# control_board.net
KiCad netlist of a schematic drawn in EasyEDA Pro
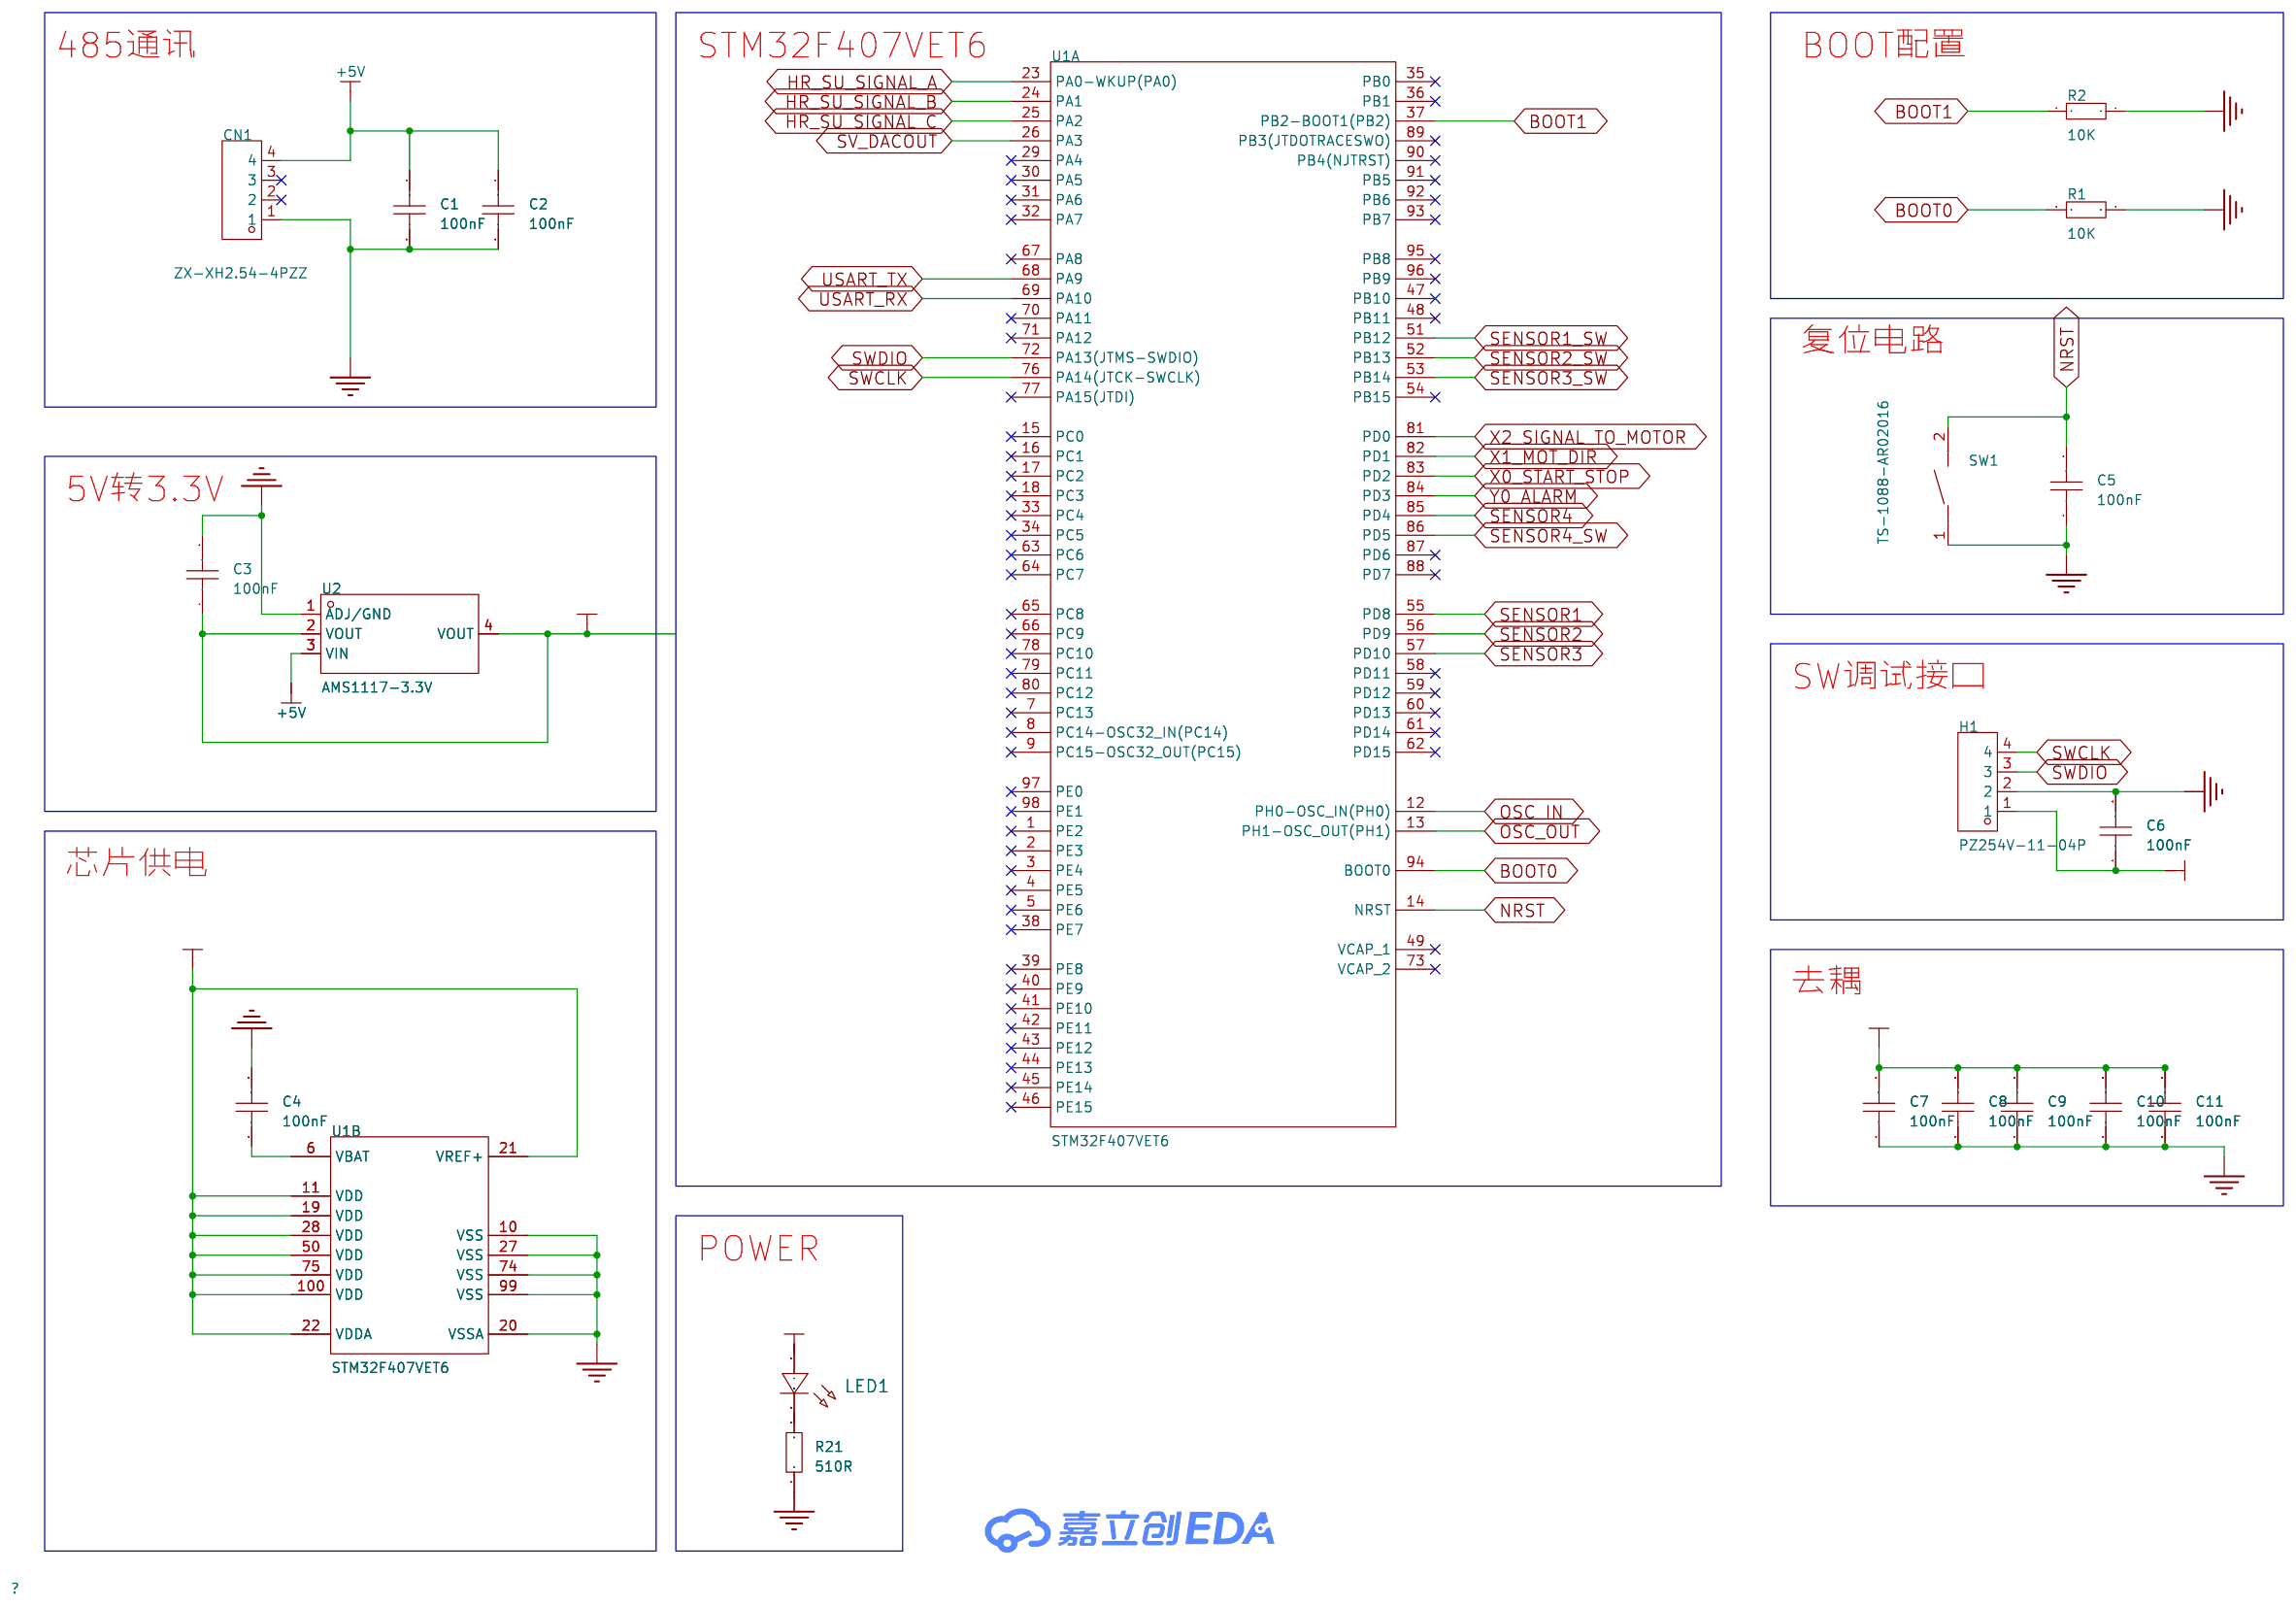
[diagram p0: P1]
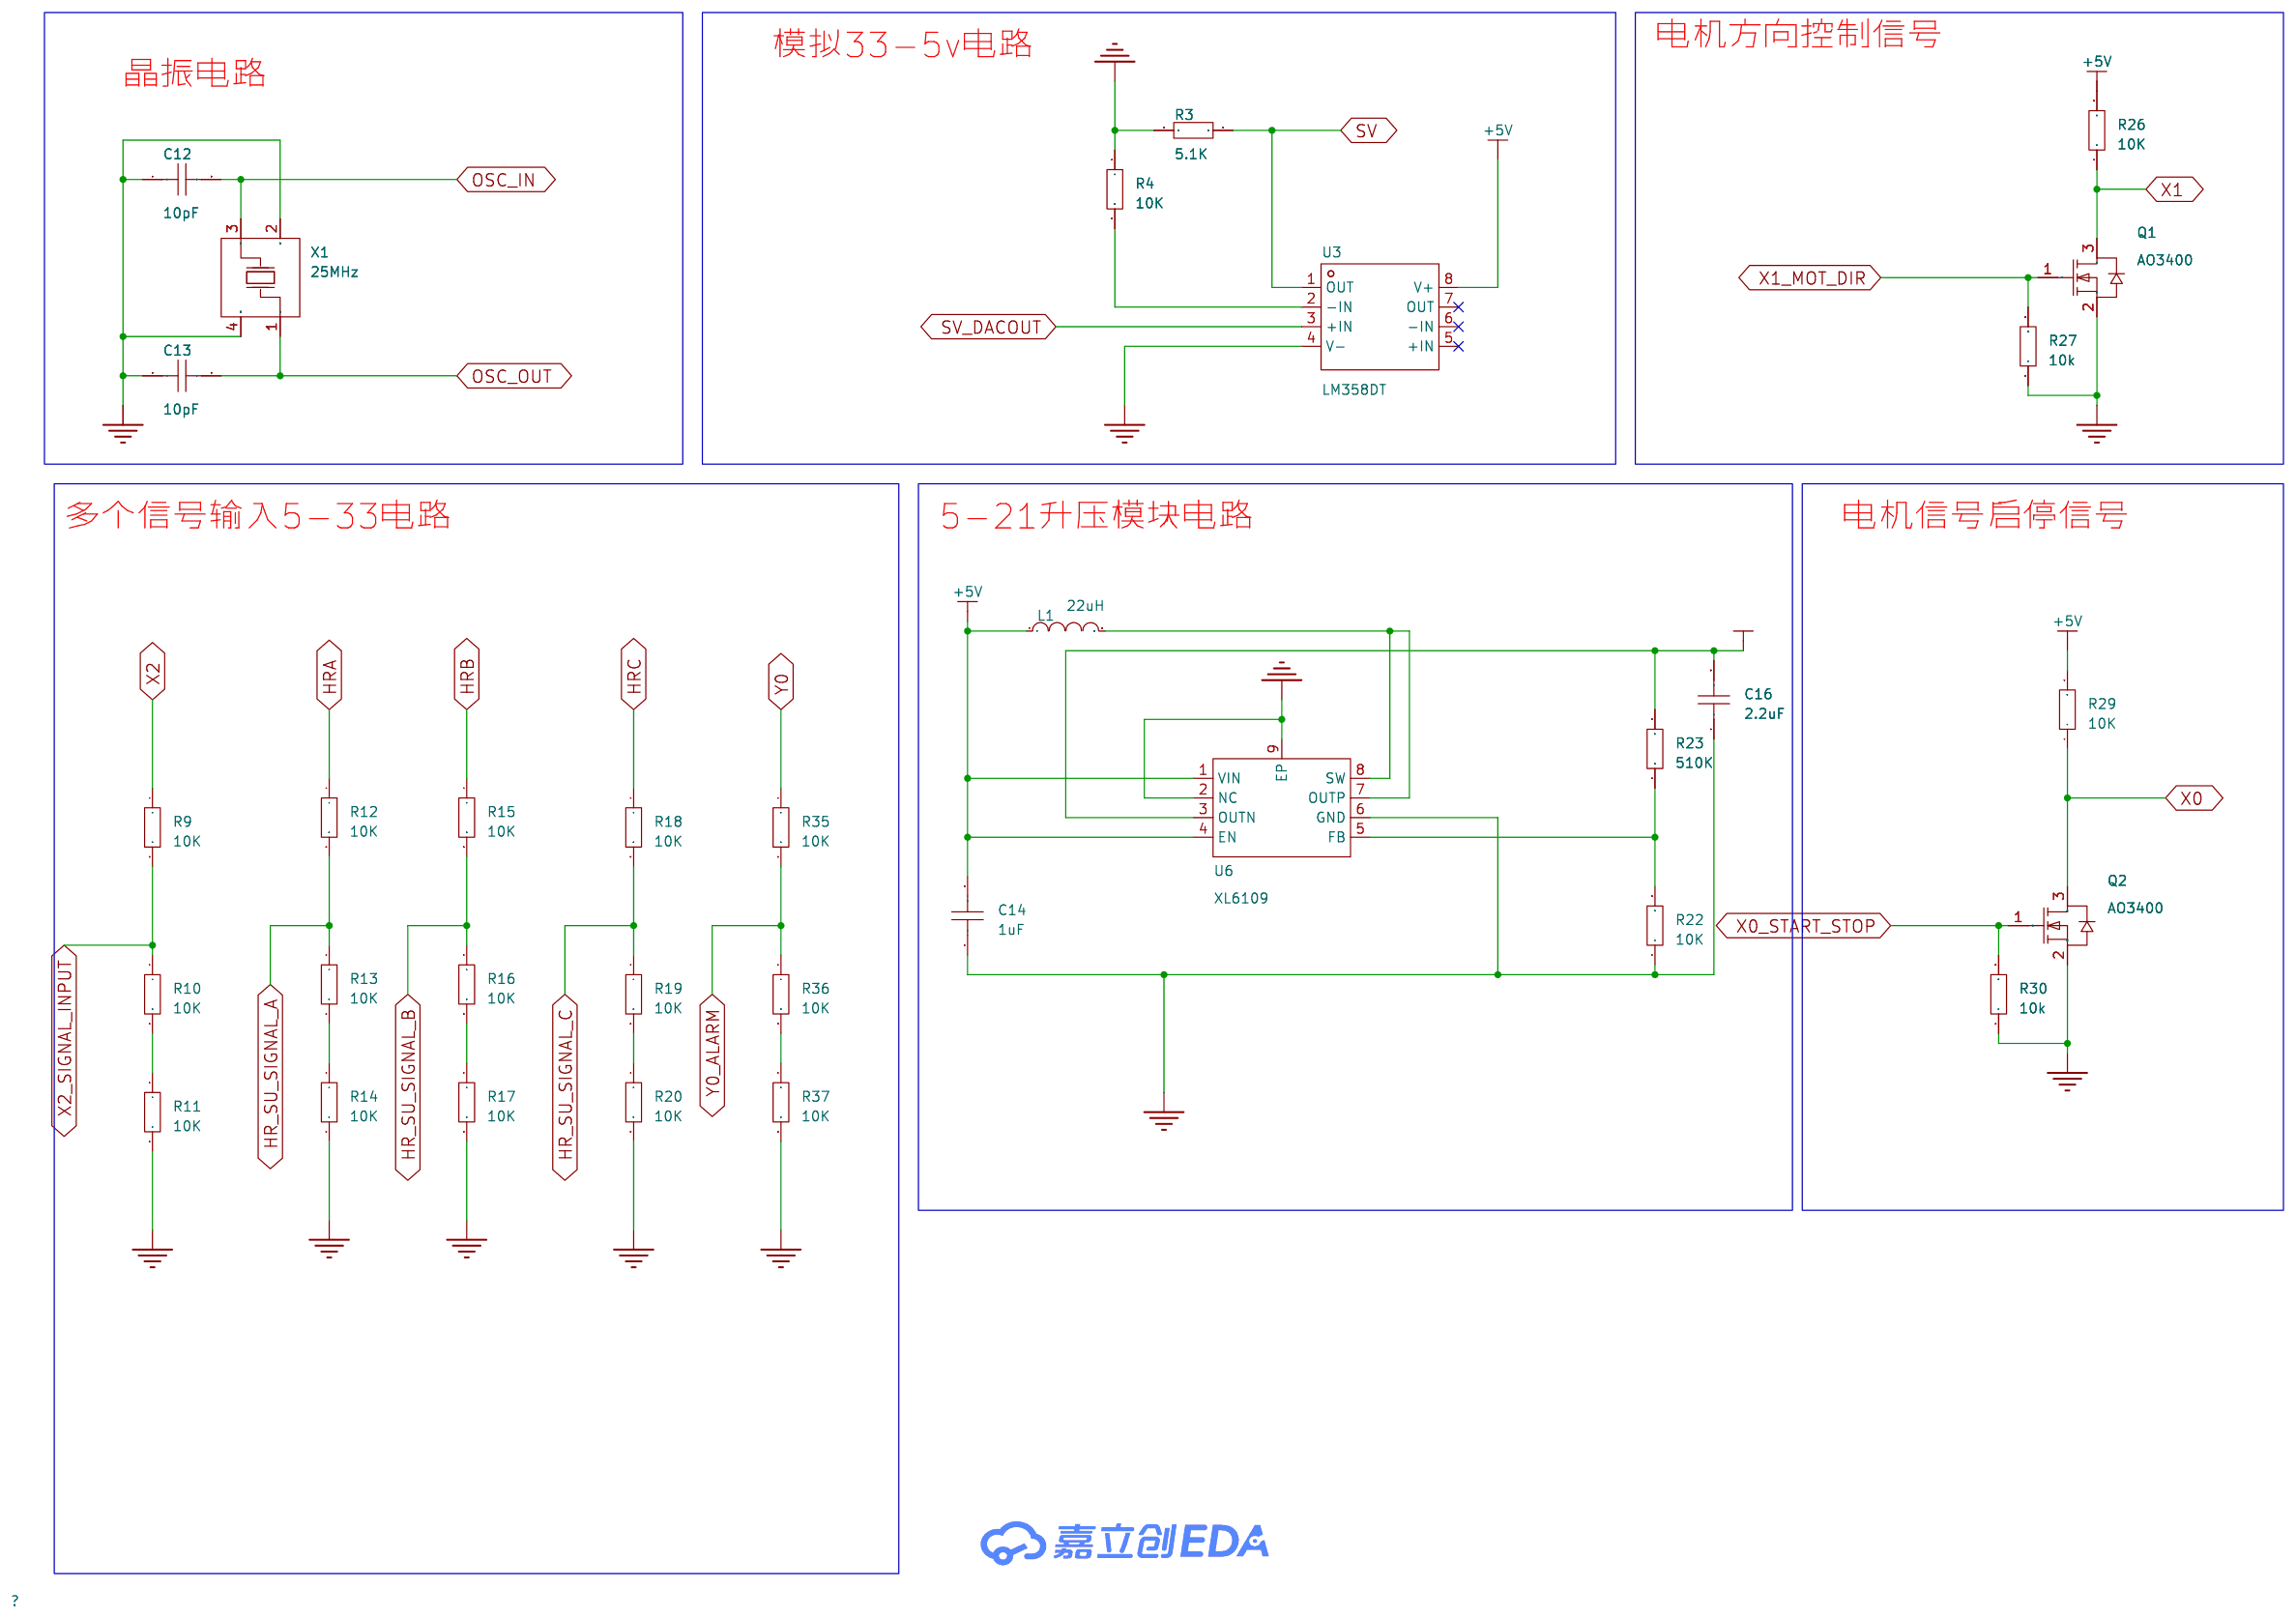
[diagram p1: P2]
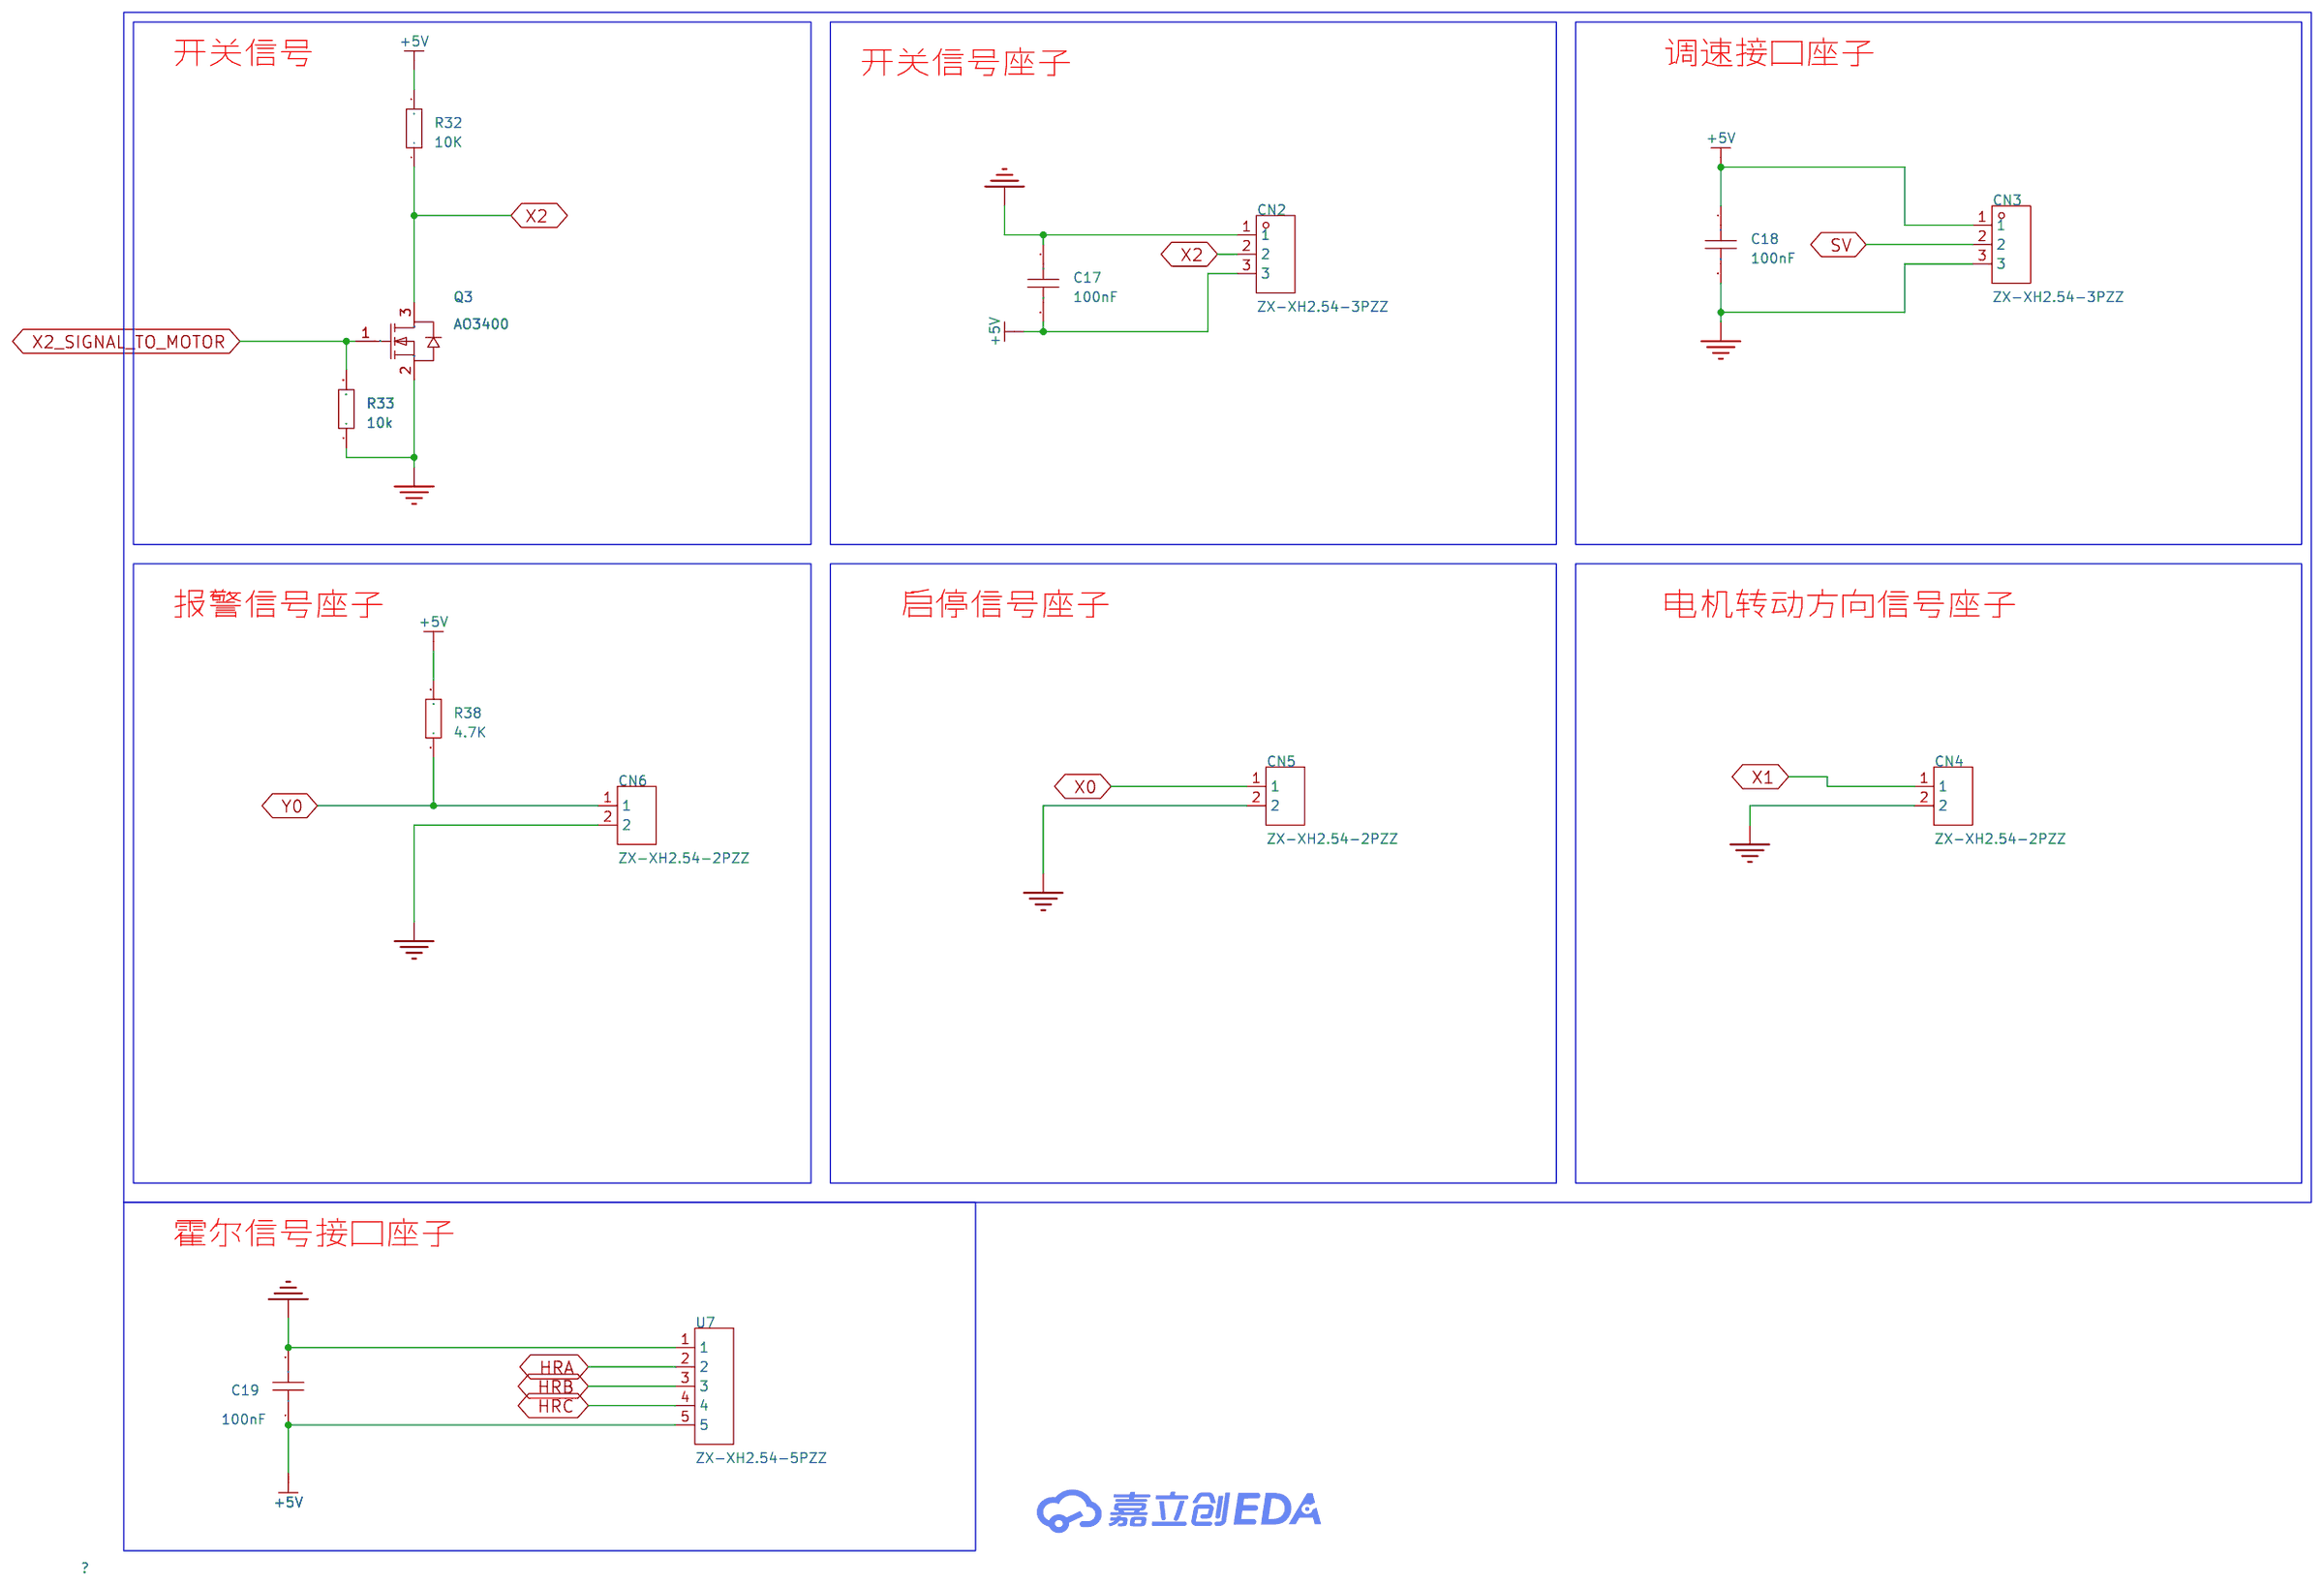
[diagram p2: P3]
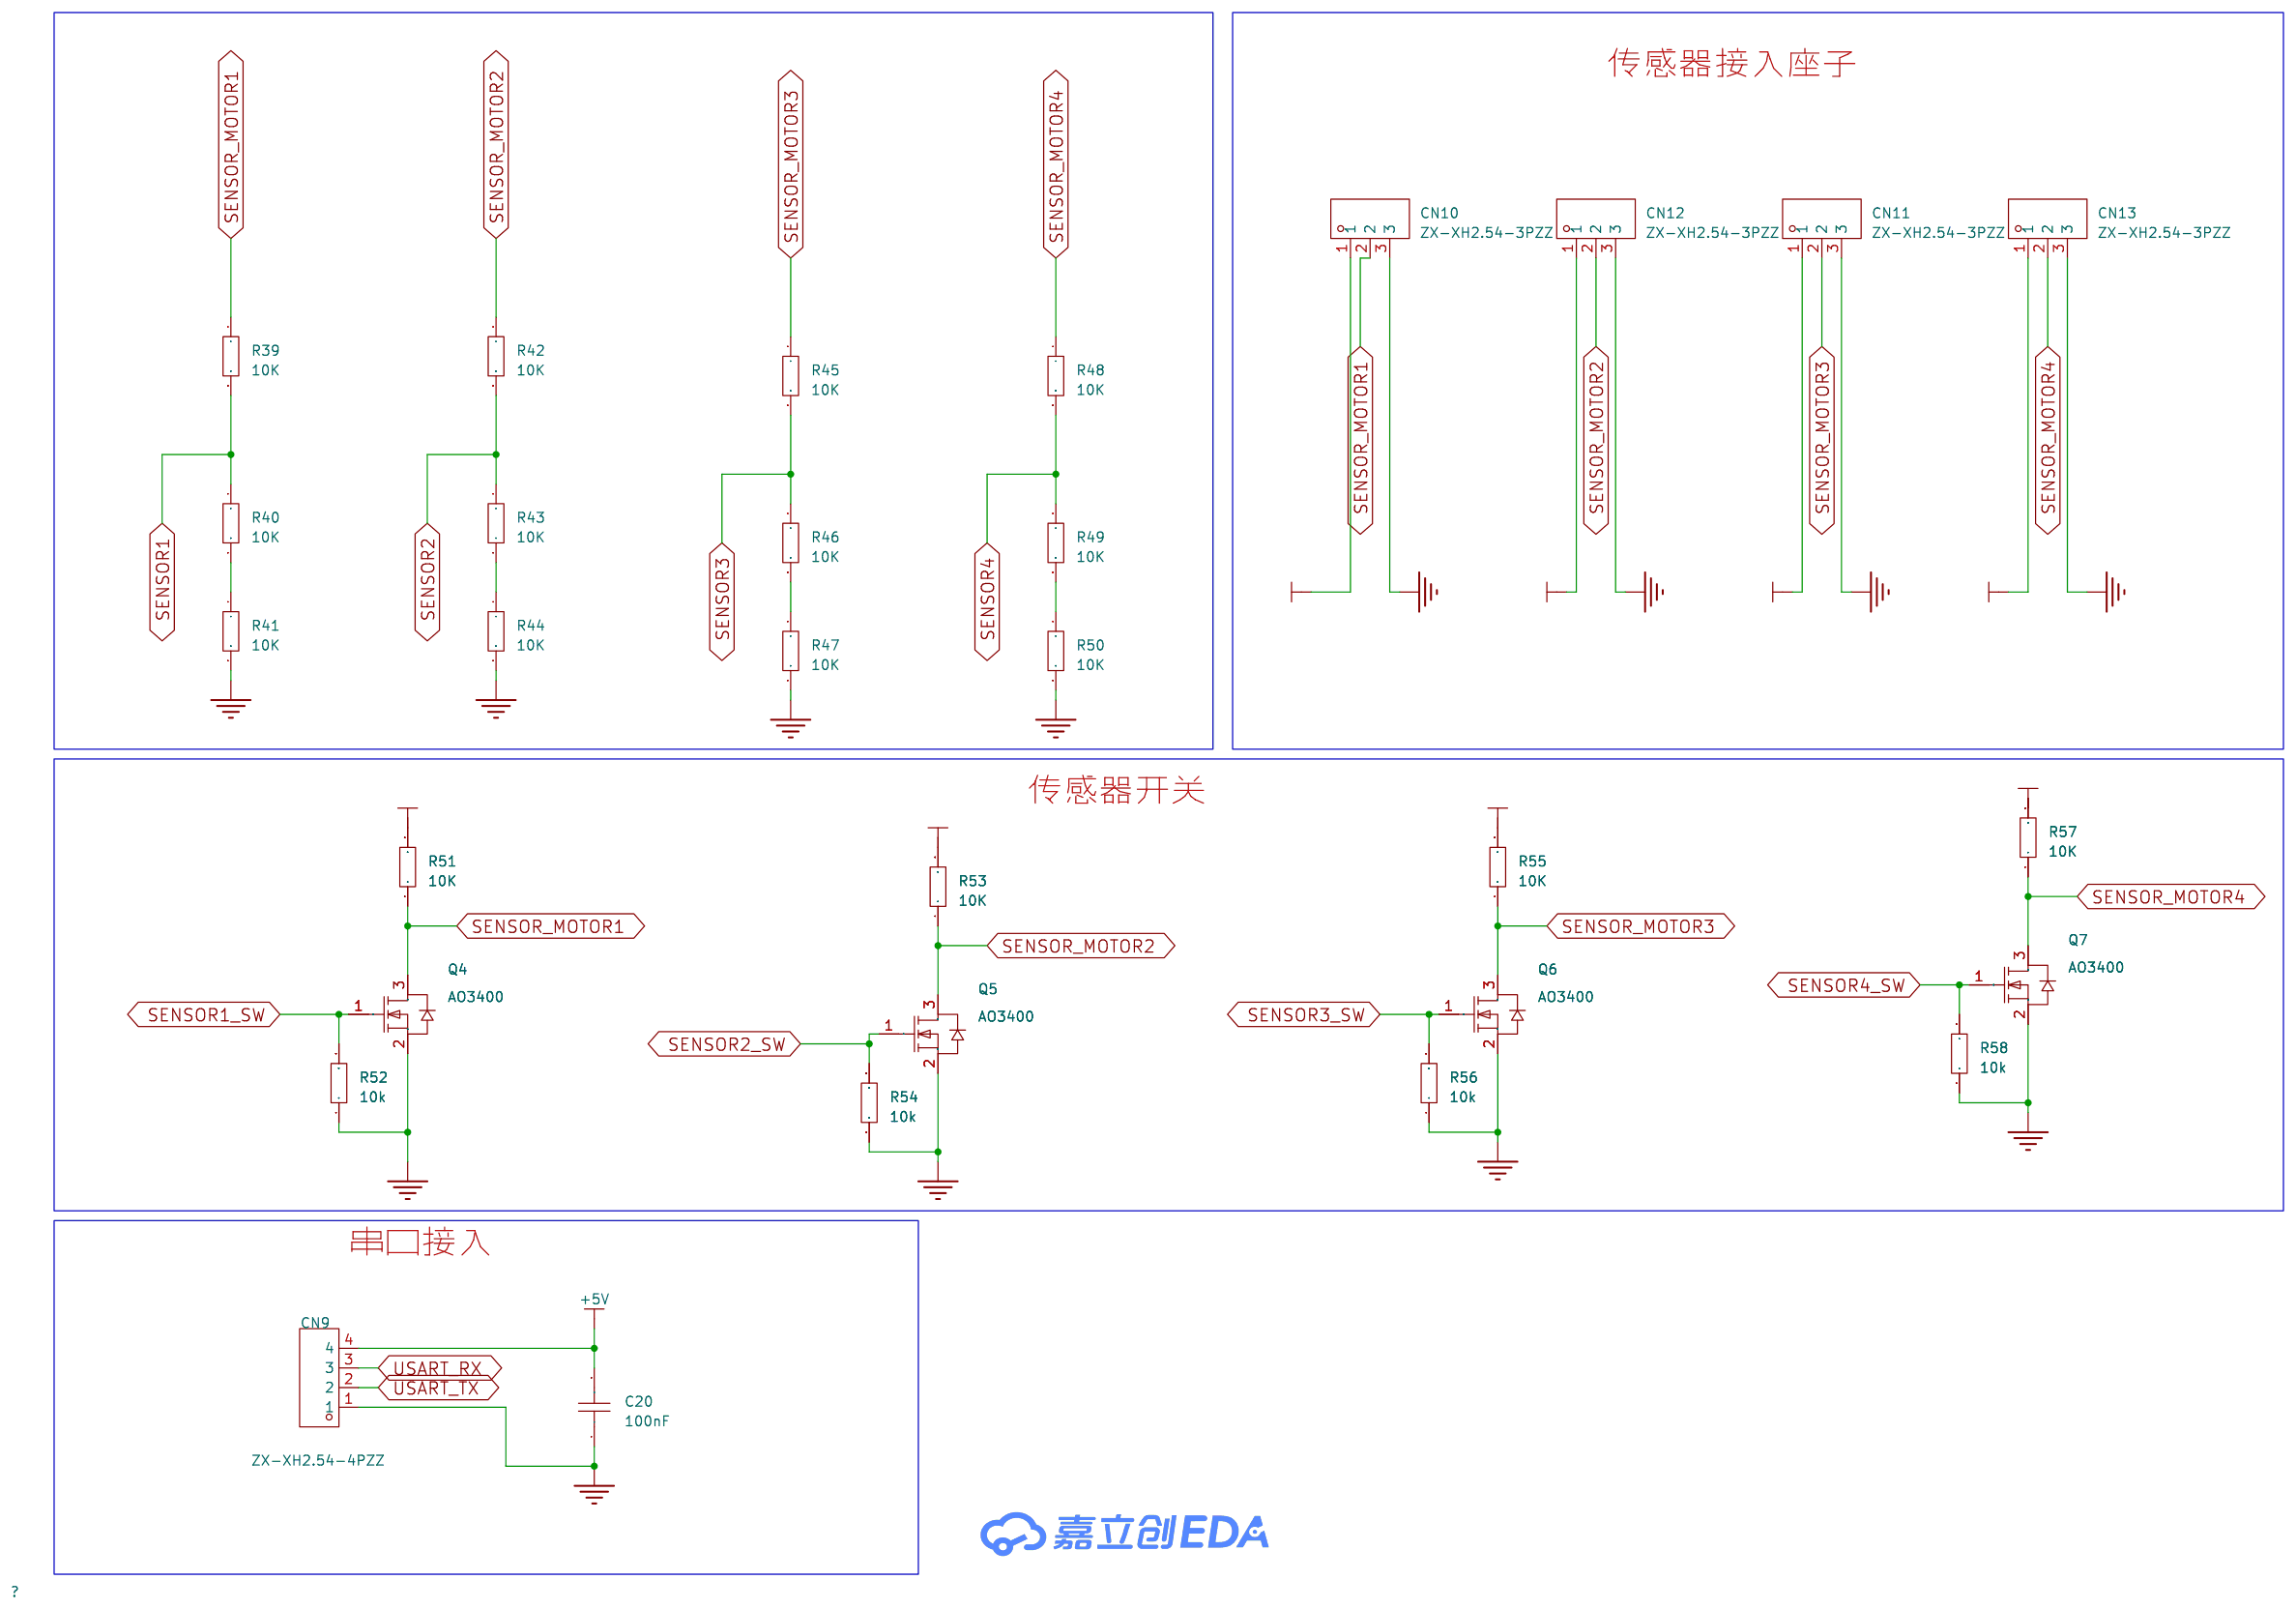
[diagram p3: P4]

(export (version "E")
  (design (tool "Eeschema 10.0.6"))
  (components
    (comp (ref "C1")
      (value "100nF")
      (footprint "easyedapro:C0603")
      (libsource (lib "easyedapro") (part "CapAcitance"))
    )
    (comp (ref "C2")
      (value "100nF")
      (footprint "easyedapro:C0603")
      (libsource (lib "easyedapro") (part "CapAcitance"))
    )
    (comp (ref "C3")
      (value "100nF")
      (footprint "easyedapro:C0603")
      (libsource (lib "easyedapro") (part "CapAcitance"))
    )
    (comp (ref "C4")
      (value "100nF")
      (footprint "easyedapro:C0603")
      (libsource (lib "easyedapro") (part "CapAcitance"))
    )
    (comp (ref "C5")
      (value "100nF")
      (footprint "easyedapro:C0603")
      (libsource (lib "easyedapro") (part "CapAcitance"))
    )
    (comp (ref "C6")
      (value "100nF")
      (footprint "easyedapro:C0603")
      (libsource (lib "easyedapro") (part "CapAcitance"))
    )
    (comp (ref "C7")
      (value "100nF")
      (footprint "easyedapro:C0603")
      (libsource (lib "easyedapro") (part "CapAcitance"))
    )
    (comp (ref "C8")
      (value "100nF")
      (footprint "easyedapro:C0603")
      (libsource (lib "easyedapro") (part "CapAcitance"))
    )
    (comp (ref "C9")
      (value "100nF")
      (footprint "easyedapro:C0603")
      (libsource (lib "easyedapro") (part "CapAcitance"))
    )
    (comp (ref "C10")
      (value "100nF")
      (footprint "easyedapro:C0603")
      (libsource (lib "easyedapro") (part "CapAcitance"))
    )
    (comp (ref "C11")
      (value "100nF")
      (footprint "easyedapro:C0603")
      (libsource (lib "easyedapro") (part "CapAcitance"))
    )
    (comp (ref "CN1")
      (value "ZX-XH2.54-4PZZ")
      (footprint "easyedapro:CONN-TH_4P-P2.50_4PIN")
      (fields (field (name "Manufacturer") "Megastar(兆星)"))
      (libsource (lib "easyedapro") (part "ZX-XH2.54-4PZZ"))
    )
    (comp (ref "H1")
      (value "PZ254V-11-04P")
      (footprint "easyedapro:HDR-TH_4P-P2.54-V-M")
      (fields (field (name "Manufacturer") "XFCN(兴飞)"))
      (libsource (lib "easyedapro") (part "PZ254V-11-04P_C2691448"))
    )
    (comp (ref "LED1")
      (value "~")
      (footprint "easyedapro:LED_0603")
      (libsource (lib "easyedapro") (part "LED_R"))
    )
    (comp (ref "R1") (value "10K") (footprint "easyedapro:R0603") (libsource (lib "easyedapro") (part "电阻")))
    (comp (ref "R2") (value "10K") (footprint "easyedapro:R0603") (libsource (lib "easyedapro") (part "电阻")))
    (comp (ref "R21")
      (value "510R")
      (footprint "easyedapro:R0603")
      (libsource (lib "easyedapro") (part "电阻"))
    )
    (comp (ref "SW1")
      (value "TS-1088-AR02016")
      (footprint "easyedapro:SW-SMD_L3.9-W3.0-P4.45")
      (fields (field (name "Manufacturer") "XUNPU(讯普)"))
      (libsource (lib "easyedapro") (part "TS-1088-AR02016"))
    )
    (comp (ref "U1")
      (value "STM32F407VET6")
      (footprint "easyedapro:LQFP-100_L14.0-W14.0-P0.50-LS16.0-BL")
      (description "CPU内核:ARM-M4;CPU最大主频:168MHz;应用领域:-;")
      (fields (field (name "Manufacturer") "ST(意法半导体)"))
      (libsource (lib "easyedapro") (part "STM32F407VET6"))
    )
    (comp (ref "U2")
      (value "AMS1117-3.3V")
      (footprint "easyedapro:SOT-223-4_L6.5-W3.5-P2.30-LS7.0-TR")
      (description "输出类型:固定;最大输入电压:18V;输出电压:3.3V;最大输出电流:1A;输出极性:正极;")
      (fields (field (name "Manufacturer") "MSKSEMI(美森科)"))
      (libsource (lib "easyedapro") (part "AMS1117-3.3V_C5120765"))
    )
    (comp (ref "C12")
      (value "10pF")
      (footprint "easyedapro:C0603")
      (libsource (lib "easyedapro") (part "CapAcitance"))
    )
    (comp (ref "C13")
      (value "10pF")
      (footprint "easyedapro:C0603")
      (libsource (lib "easyedapro") (part "CapAcitance"))
    )
    (comp (ref "C14")
      (value "1uF")
      (footprint "easyedapro:C0603")
      (libsource (lib "easyedapro") (part "CapAcitance"))
    )
    (comp (ref "C16")
      (value "2.2uF")
      (footprint "easyedapro:C0603")
      (libsource (lib "easyedapro") (part "CapAcitance"))
    )
    (comp (ref "L1")
      (value "22uH")
      (footprint "easyedapro:L0603")
      (libsource (lib "easyedapro") (part "SDFL1608S100KTF"))
    )
    (comp (ref "Q1")
      (value "AO3400")
      (footprint "easyedapro:SOT-23_L2.9-W1.3-P1.90-LS2.4-BR")
      (fields (field (name "Manufacturer") "GOODWORK(固得沃克)"))
      (libsource (lib "easyedapro") (part "AO3400_C2938367"))
    )
    (comp (ref "Q2")
      (value "AO3400")
      (footprint "easyedapro:SOT-23_L2.9-W1.3-P1.90-LS2.4-BR")
      (fields (field (name "Manufacturer") "GOODWORK(固得沃克)"))
      (libsource (lib "easyedapro") (part "AO3400_C2938367"))
    )
    (comp (ref "R3") (value "5.1K") (footprint "easyedapro:R0603") (libsource (lib "easyedapro") (part "电阻")))
    (comp (ref "R4") (value "10K") (footprint "easyedapro:R0603") (libsource (lib "easyedapro") (part "电阻")))
    (comp (ref "R9") (value "10K") (footprint "easyedapro:R0603") (libsource (lib "easyedapro") (part "电阻")))
    (comp (ref "R10") (value "10K") (footprint "easyedapro:R0603") (libsource (lib "easyedapro") (part "电阻")))
    (comp (ref "R11") (value "10K") (footprint "easyedapro:R0603") (libsource (lib "easyedapro") (part "电阻")))
    (comp (ref "R12") (value "10K") (footprint "easyedapro:R0603") (libsource (lib "easyedapro") (part "电阻")))
    (comp (ref "R13") (value "10K") (footprint "easyedapro:R0603") (libsource (lib "easyedapro") (part "电阻")))
    (comp (ref "R14") (value "10K") (footprint "easyedapro:R0603") (libsource (lib "easyedapro") (part "电阻")))
    (comp (ref "R15") (value "10K") (footprint "easyedapro:R0603") (libsource (lib "easyedapro") (part "电阻")))
    (comp (ref "R16") (value "10K") (footprint "easyedapro:R0603") (libsource (lib "easyedapro") (part "电阻")))
    (comp (ref "R17") (value "10K") (footprint "easyedapro:R0603") (libsource (lib "easyedapro") (part "电阻")))
    (comp (ref "R18") (value "10K") (footprint "easyedapro:R0603") (libsource (lib "easyedapro") (part "电阻")))
    (comp (ref "R19") (value "10K") (footprint "easyedapro:R0603") (libsource (lib "easyedapro") (part "电阻")))
    (comp (ref "R20") (value "10K") (footprint "easyedapro:R0603") (libsource (lib "easyedapro") (part "电阻")))
    (comp (ref "R22") (value "10K") (footprint "easyedapro:R0603") (libsource (lib "easyedapro") (part "电阻")))
    (comp (ref "R23")
      (value "510K")
      (footprint "easyedapro:R0603")
      (libsource (lib "easyedapro") (part "电阻"))
    )
    (comp (ref "R26") (value "10K") (footprint "easyedapro:R0603") (libsource (lib "easyedapro") (part "电阻")))
    (comp (ref "R27") (value "10k") (footprint "easyedapro:R0603") (libsource (lib "easyedapro") (part "电阻")))
    (comp (ref "R29") (value "10K") (footprint "easyedapro:R0603") (libsource (lib "easyedapro") (part "电阻")))
    (comp (ref "R30") (value "10k") (footprint "easyedapro:R0603") (libsource (lib "easyedapro") (part "电阻")))
    (comp (ref "R35") (value "10K") (footprint "easyedapro:R0603") (libsource (lib "easyedapro") (part "电阻")))
    (comp (ref "R36") (value "10K") (footprint "easyedapro:R0603") (libsource (lib "easyedapro") (part "电阻")))
    (comp (ref "R37") (value "10K") (footprint "easyedapro:R0603") (libsource (lib "easyedapro") (part "电阻")))
    (comp (ref "U3")
      (value "LM358DT")
      (footprint "easyedapro:SOIC-8_L5.0-W4.0-P1.27-LS6.0-BL")
      (description "放大器数:双路;轨到轨:-;增益带宽积(GBP):-;输入失调电压(Vos):7mV;压摆率(SR):600V/ms;输入偏置电流(Ib):200nA;")
      (fields (field (name "Manufacturer") "ST(意法半导体)"))
      (libsource (lib "easyedapro") (part "LM358DT"))
    )
    (comp (ref "U6")
      (value "XL6109")
      (footprint "easyedapro:DFN-8_L3.0-W3.0-P0.50-TL-EP2.1")
      (description "升压，内置，输入2.5-25V,输出3V-32V,0.6A,1.2MHz")
      (fields (field (name "Manufacturer") "XLSEMI(芯龙)"))
      (libsource (lib "easyedapro") (part "XL6109"))
    )
    (comp (ref "X1")
      (value "25MHz")
      (footprint "easyedapro:CRYSTAL-SMD_4P-L3.2-W2.5-BL")
      (description "晶振类型:贴片晶振;频率:25MHz;常温频差:±10ppm;负载电容:12pF;频率稳定度:±20ppm;")
      (fields (field (name "Manufacturer Part") "X322525MOB4SI") (field (name "Manufacturer") "YXC(扬兴晶振)"))
      (libsource (lib "easyedapro") (part "X322525MOB4SI"))
    )
    (comp (ref "C17")
      (value "100nF")
      (footprint "easyedapro:C0603")
      (libsource (lib "easyedapro") (part "CapAcitance"))
    )
    (comp (ref "C18")
      (value "100nF")
      (footprint "easyedapro:C0603")
      (libsource (lib "easyedapro") (part "CapAcitance"))
    )
    (comp (ref "C19")
      (value "100nF")
      (footprint "easyedapro:C0603")
      (libsource (lib "easyedapro") (part "CapAcitance"))
    )
    (comp (ref "CN2")
      (value "ZX-XH2.54-3PZZ")
      (footprint "easyedapro:CONN-TH_3P-P2.54_2501S-3P")
      (fields (field (name "Manufacturer") "Megastar(兆星)"))
      (libsource (lib "easyedapro") (part "ZX-XH2.54-3PZZ"))
    )
    (comp (ref "CN3")
      (value "ZX-XH2.54-3PZZ")
      (footprint "easyedapro:CONN-TH_3P-P2.54_2501S-3P")
      (fields (field (name "Manufacturer") "Megastar(兆星)"))
      (libsource (lib "easyedapro") (part "ZX-XH2.54-3PZZ"))
    )
    (comp (ref "CN4")
      (value "ZX-XH2.54-2PZZ")
      (footprint "easyedapro:CONN-TH_2P-P2.50_HX25003-2A")
      (fields (field (name "Manufacturer") "Megastar(兆星)"))
      (libsource (lib "easyedapro") (part "ZX-XH2.54-2PZZ"))
    )
    (comp (ref "CN5")
      (value "ZX-XH2.54-2PZZ")
      (footprint "easyedapro:CONN-TH_2P-P2.50_HX25003-2A")
      (fields (field (name "Manufacturer") "Megastar(兆星)"))
      (libsource (lib "easyedapro") (part "ZX-XH2.54-2PZZ"))
    )
    (comp (ref "CN6")
      (value "ZX-XH2.54-2PZZ")
      (footprint "easyedapro:CONN-TH_2P-P2.50_HX25003-2A")
      (fields (field (name "Manufacturer") "Megastar(兆星)"))
      (libsource (lib "easyedapro") (part "ZX-XH2.54-2PZZ"))
    )
    (comp (ref "Q3")
      (value "AO3400")
      (footprint "easyedapro:SOT-23_L2.9-W1.3-P1.90-LS2.4-BR")
      (fields (field (name "Manufacturer") "GOODWORK(固得沃克)"))
      (libsource (lib "easyedapro") (part "AO3400_C2938367"))
    )
    (comp (ref "R32") (value "10K") (footprint "easyedapro:R0603") (libsource (lib "easyedapro") (part "电阻")))
    (comp (ref "R33") (value "10k") (footprint "easyedapro:R0603") (libsource (lib "easyedapro") (part "电阻")))
    (comp (ref "R38")
      (value "4.7K")
      (footprint "easyedapro:R0603")
      (libsource (lib "easyedapro") (part "电阻"))
    )
    (comp (ref "U7")
      (value "ZX-XH2.54-5PZZ")
      (footprint "easyedapro:CONN-TH_5P-P2.50_ZX-XH2.54-5PZZ")
      (fields (field (name "Manufacturer") "Megastar(兆星)"))
      (libsource (lib "easyedapro") (part "ZX-XH2.54-5PZZ"))
    )
    (comp (ref "C20")
      (value "100nF")
      (footprint "easyedapro:C0603")
      (libsource (lib "easyedapro") (part "CapAcitance"))
    )
    (comp (ref "CN9")
      (value "ZX-XH2.54-4PZZ")
      (footprint "easyedapro:CONN-TH_4P-P2.50_4PIN")
      (fields (field (name "Manufacturer") "Megastar(兆星)"))
      (libsource (lib "easyedapro") (part "ZX-XH2.54-4PZZ"))
    )
    (comp (ref "CN10")
      (value "ZX-XH2.54-3PZZ")
      (footprint "easyedapro:CONN-TH_3P-P2.54_2501S-3P")
      (fields (field (name "Manufacturer") "Megastar(兆星)"))
      (libsource (lib "easyedapro") (part "ZX-XH2.54-3PZZ"))
    )
    (comp (ref "CN11")
      (value "ZX-XH2.54-3PZZ")
      (footprint "easyedapro:CONN-TH_3P-P2.54_2501S-3P")
      (fields (field (name "Manufacturer") "Megastar(兆星)"))
      (libsource (lib "easyedapro") (part "ZX-XH2.54-3PZZ"))
    )
    (comp (ref "CN12")
      (value "ZX-XH2.54-3PZZ")
      (footprint "easyedapro:CONN-TH_3P-P2.54_2501S-3P")
      (fields (field (name "Manufacturer") "Megastar(兆星)"))
      (libsource (lib "easyedapro") (part "ZX-XH2.54-3PZZ"))
    )
    (comp (ref "CN13")
      (value "ZX-XH2.54-3PZZ")
      (footprint "easyedapro:CONN-TH_3P-P2.54_2501S-3P")
      (fields (field (name "Manufacturer") "Megastar(兆星)"))
      (libsource (lib "easyedapro") (part "ZX-XH2.54-3PZZ"))
    )
    (comp (ref "Q4")
      (value "AO3400")
      (footprint "easyedapro:SOT-23_L2.9-W1.3-P1.90-LS2.4-BR")
      (fields (field (name "Manufacturer") "GOODWORK(固得沃克)"))
      (libsource (lib "easyedapro") (part "AO3400_C2938367"))
    )
    (comp (ref "Q5")
      (value "AO3400")
      (footprint "easyedapro:SOT-23_L2.9-W1.3-P1.90-LS2.4-BR")
      (fields (field (name "Manufacturer") "GOODWORK(固得沃克)"))
      (libsource (lib "easyedapro") (part "AO3400_C2938367"))
    )
    (comp (ref "Q6")
      (value "AO3400")
      (footprint "easyedapro:SOT-23_L2.9-W1.3-P1.90-LS2.4-BR")
      (fields (field (name "Manufacturer") "GOODWORK(固得沃克)"))
      (libsource (lib "easyedapro") (part "AO3400_C2938367"))
    )
    (comp (ref "Q7")
      (value "AO3400")
      (footprint "easyedapro:SOT-23_L2.9-W1.3-P1.90-LS2.4-BR")
      (fields (field (name "Manufacturer") "GOODWORK(固得沃克)"))
      (libsource (lib "easyedapro") (part "AO3400_C2938367"))
    )
    (comp (ref "R39") (value "10K") (footprint "easyedapro:R0603") (libsource (lib "easyedapro") (part "电阻")))
    (comp (ref "R40") (value "10K") (footprint "easyedapro:R0603") (libsource (lib "easyedapro") (part "电阻")))
    (comp (ref "R41") (value "10K") (footprint "easyedapro:R0603") (libsource (lib "easyedapro") (part "电阻")))
    (comp (ref "R42") (value "10K") (footprint "easyedapro:R0603") (libsource (lib "easyedapro") (part "电阻")))
    (comp (ref "R43") (value "10K") (footprint "easyedapro:R0603") (libsource (lib "easyedapro") (part "电阻")))
    (comp (ref "R44") (value "10K") (footprint "easyedapro:R0603") (libsource (lib "easyedapro") (part "电阻")))
    (comp (ref "R45") (value "10K") (footprint "easyedapro:R0603") (libsource (lib "easyedapro") (part "电阻")))
    (comp (ref "R46") (value "10K") (footprint "easyedapro:R0603") (libsource (lib "easyedapro") (part "电阻")))
    (comp (ref "R47") (value "10K") (footprint "easyedapro:R0603") (libsource (lib "easyedapro") (part "电阻")))
    (comp (ref "R48") (value "10K") (footprint "easyedapro:R0603") (libsource (lib "easyedapro") (part "电阻")))
    (comp (ref "R49") (value "10K") (footprint "easyedapro:R0603") (libsource (lib "easyedapro") (part "电阻")))
    (comp (ref "R50") (value "10K") (footprint "easyedapro:R0603") (libsource (lib "easyedapro") (part "电阻")))
    (comp (ref "R51") (value "10K") (footprint "easyedapro:R0603") (libsource (lib "easyedapro") (part "电阻")))
    (comp (ref "R52") (value "10k") (footprint "easyedapro:R0603") (libsource (lib "easyedapro") (part "电阻")))
    (comp (ref "R53") (value "10K") (footprint "easyedapro:R0603") (libsource (lib "easyedapro") (part "电阻")))
    (comp (ref "R54") (value "10k") (footprint "easyedapro:R0603") (libsource (lib "easyedapro") (part "电阻")))
    (comp (ref "R55") (value "10K") (footprint "easyedapro:R0603") (libsource (lib "easyedapro") (part "电阻")))
    (comp (ref "R56") (value "10k") (footprint "easyedapro:R0603") (libsource (lib "easyedapro") (part "电阻")))
    (comp (ref "R57") (value "10K") (footprint "easyedapro:R0603") (libsource (lib "easyedapro") (part "电阻")))
    (comp (ref "R58") (value "10k") (footprint "easyedapro:R0603") (libsource (lib "easyedapro") (part "电阻")))
  )
  (nets
    (net (code "1") (name "+5V") (class "Default")
      (node (ref "C1") (pin "1") (pinfunction "1_1") (pintype "input"))
      (node (ref "C14") (pin "2") (pinfunction "2_2") (pintype "input"))
      (node (ref "C17") (pin "2") (pinfunction "2_2") (pintype "input"))
      (node (ref "C18") (pin "1") (pinfunction "1_1") (pintype "input"))
      (node (ref "C19") (pin "1") (pinfunction "1_1") (pintype "input"))
      (node (ref "C2") (pin "1") (pinfunction "1_1") (pintype "input"))
      (node (ref "C20") (pin "2") (pinfunction "2_2") (pintype "input"))
      (node (ref "CN1") (pin "4") (pinfunction "4_4") (pintype "unspecified"))
      (node (ref "CN2") (pin "3") (pinfunction "3_3") (pintype "unspecified"))
      (node (ref "CN3") (pin "1") (pinfunction "1_1") (pintype "unspecified"))
      (node (ref "CN9") (pin "4") (pinfunction "4_4") (pintype "unspecified"))
      (node (ref "L1") (pin "1") (pinfunction "1_1") (pintype "unspecified"))
      (node (ref "R26") (pin "2") (pinfunction "2_2") (pintype "input"))
      (node (ref "R29") (pin "2") (pinfunction "2_2") (pintype "input"))
      (node (ref "R32") (pin "2") (pinfunction "2_2") (pintype "input"))
      (node (ref "R38") (pin "2") (pinfunction "2_2") (pintype "input"))
      (node (ref "U2") (pin "3") (pinfunction "VIN_3") (pintype "unspecified"))
      (node (ref "U3") (pin "8") (pinfunction "V+_8") (pintype "unspecified"))
      (node (ref "U6") (pin "1") (pinfunction "VIN_1") (pintype "unspecified"))
      (node (ref "U6") (pin "4") (pinfunction "EN_4") (pintype "unspecified"))
      (node (ref "U7") (pin "5") (pinfunction "5_5") (pintype "unspecified"))
    )
    (net (code "2") (name "BOOT0") (class "Default")
      (node (ref "R1") (pin "2") (pinfunction "2_2") (pintype "input"))
      (node (ref "U1") (pin "94") (pinfunction "BOOT0_94") (pintype "unspecified"))
    )
    (net (code "3") (name "BOOT1") (class "Default")
      (node (ref "R2") (pin "2") (pinfunction "2_2") (pintype "input"))
      (node (ref "U1") (pin "37") (pinfunction "PB2-BOOT1(PB2)_37") (pintype "bidirectional"))
    )
    (net (code "4") (name "GND") (class "Default")
      (node (ref "C1") (pin "2") (pinfunction "2_2") (pintype "input"))
      (node (ref "C10") (pin "1") (pinfunction "1_1") (pintype "input"))
      (node (ref "C11") (pin "1") (pinfunction "1_1") (pintype "input"))
      (node (ref "C12") (pin "1") (pinfunction "1_1") (pintype "input"))
      (node (ref "C13") (pin "1") (pinfunction "1_1") (pintype "input"))
      (node (ref "C14") (pin "1") (pinfunction "1_1") (pintype "input"))
      (node (ref "C16") (pin "1") (pinfunction "1_1") (pintype "input"))
      (node (ref "C17") (pin "1") (pinfunction "1_1") (pintype "input"))
      (node (ref "C18") (pin "2") (pinfunction "2_2") (pintype "input"))
      (node (ref "C19") (pin "2") (pinfunction "2_2") (pintype "input"))
      (node (ref "C2") (pin "2") (pinfunction "2_2") (pintype "input"))
      (node (ref "C20") (pin "1") (pinfunction "1_1") (pintype "input"))
      (node (ref "C3") (pin "2") (pinfunction "2_2") (pintype "input"))
      (node (ref "C4") (pin "2") (pinfunction "2_2") (pintype "input"))
      (node (ref "C5") (pin "1") (pinfunction "1_1") (pintype "input"))
      (node (ref "C6") (pin "2") (pinfunction "2_2") (pintype "input"))
      (node (ref "C7") (pin "1") (pinfunction "1_1") (pintype "input"))
      (node (ref "C8") (pin "1") (pinfunction "1_1") (pintype "input"))
      (node (ref "C9") (pin "1") (pinfunction "1_1") (pintype "input"))
      (node (ref "CN1") (pin "1") (pinfunction "1_1") (pintype "unspecified"))
      (node (ref "CN10") (pin "3") (pinfunction "3_3") (pintype "unspecified"))
      (node (ref "CN11") (pin "3") (pinfunction "3_3") (pintype "unspecified"))
      (node (ref "CN12") (pin "3") (pinfunction "3_3") (pintype "unspecified"))
      (node (ref "CN13") (pin "3") (pinfunction "3_3") (pintype "unspecified"))
      (node (ref "CN2") (pin "1") (pinfunction "1_1") (pintype "unspecified"))
      (node (ref "CN3") (pin "3") (pinfunction "3_3") (pintype "unspecified"))
      (node (ref "CN4") (pin "2") (pinfunction "2_2") (pintype "unspecified"))
      (node (ref "CN5") (pin "2") (pinfunction "2_2") (pintype "unspecified"))
      (node (ref "CN6") (pin "2") (pinfunction "2_2") (pintype "unspecified"))
      (node (ref "CN9") (pin "1") (pinfunction "1_1") (pintype "unspecified"))
      (node (ref "H1") (pin "2") (pinfunction "2_2") (pintype "unspecified"))
      (node (ref "Q1") (pin "2") (pinfunction "S_2") (pintype "unspecified"))
      (node (ref "Q2") (pin "2") (pinfunction "S_2") (pintype "unspecified"))
      (node (ref "Q3") (pin "2") (pinfunction "S_2") (pintype "unspecified"))
      (node (ref "Q4") (pin "2") (pinfunction "S_2") (pintype "unspecified"))
      (node (ref "Q5") (pin "2") (pinfunction "S_2") (pintype "unspecified"))
      (node (ref "Q6") (pin "2") (pinfunction "S_2") (pintype "unspecified"))
      (node (ref "Q7") (pin "2") (pinfunction "S_2") (pintype "unspecified"))
      (node (ref "R1") (pin "1") (pinfunction "1_1") (pintype "input"))
      (node (ref "R11") (pin "2") (pinfunction "2_2") (pintype "input"))
      (node (ref "R14") (pin "2") (pinfunction "2_2") (pintype "input"))
      (node (ref "R17") (pin "2") (pinfunction "2_2") (pintype "input"))
      (node (ref "R2") (pin "1") (pinfunction "1_1") (pintype "input"))
      (node (ref "R20") (pin "2") (pinfunction "2_2") (pintype "input"))
      (node (ref "R21") (pin "1") (pinfunction "1_1") (pintype "input"))
      (node (ref "R22") (pin "1") (pinfunction "1_1") (pintype "input"))
      (node (ref "R27") (pin "1") (pinfunction "1_1") (pintype "input"))
      (node (ref "R3") (pin "1") (pinfunction "1_1") (pintype "input"))
      (node (ref "R30") (pin "1") (pinfunction "1_1") (pintype "input"))
      (node (ref "R33") (pin "1") (pinfunction "1_1") (pintype "input"))
      (node (ref "R37") (pin "2") (pinfunction "2_2") (pintype "input"))
      (node (ref "R4") (pin "1") (pinfunction "1_1") (pintype "input"))
      (node (ref "R41") (pin "2") (pinfunction "2_2") (pintype "input"))
      (node (ref "R44") (pin "2") (pinfunction "2_2") (pintype "input"))
      (node (ref "R47") (pin "2") (pinfunction "2_2") (pintype "input"))
      (node (ref "R50") (pin "2") (pinfunction "2_2") (pintype "input"))
      (node (ref "R52") (pin "1") (pinfunction "1_1") (pintype "input"))
      (node (ref "R54") (pin "1") (pinfunction "1_1") (pintype "input"))
      (node (ref "R56") (pin "1") (pinfunction "1_1") (pintype "input"))
      (node (ref "R58") (pin "1") (pinfunction "1_1") (pintype "input"))
      (node (ref "SW1") (pin "1") (pinfunction "1_1") (pintype "unspecified"))
      (node (ref "U1") (pin "10") (pinfunction "VSS_10") (pintype "unspecified"))
      (node (ref "U1") (pin "20") (pinfunction "VSSA_20") (pintype "unspecified"))
      (node (ref "U1") (pin "27") (pinfunction "VSS_27") (pintype "unspecified"))
      (node (ref "U1") (pin "74") (pinfunction "VSS_74") (pintype "unspecified"))
      (node (ref "U1") (pin "99") (pinfunction "VSS_99") (pintype "unspecified"))
      (node (ref "U2") (pin "1") (pinfunction "ADJ/GND_1") (pintype "unspecified"))
      (node (ref "U3") (pin "4") (pinfunction "V-_4") (pintype "unspecified"))
      (node (ref "U6") (pin "2") (pinfunction "NC_2") (pintype "unspecified"))
      (node (ref "U6") (pin "6") (pinfunction "GND_6") (pintype "unspecified"))
      (node (ref "U6") (pin "9") (pinfunction "EP_9") (pintype "unspecified"))
      (node (ref "U7") (pin "1") (pinfunction "1_1") (pintype "unspecified"))
      (node (ref "X1") (pin "2") (pinfunction "GND_2") (pintype "unspecified"))
      (node (ref "X1") (pin "4") (pinfunction "GND_4") (pintype "unspecified"))
    )
    (net (code "5") (name "HRA") (class "Default")
      (node (ref "R12") (pin "1") (pinfunction "1_1") (pintype "input"))
      (node (ref "U7") (pin "2") (pinfunction "2_2") (pintype "unspecified"))
    )
    (net (code "6") (name "HRB") (class "Default")
      (node (ref "R15") (pin "1") (pinfunction "1_1") (pintype "input"))
      (node (ref "U7") (pin "3") (pinfunction "3_3") (pintype "unspecified"))
    )
    (net (code "7") (name "HRC") (class "Default")
      (node (ref "R18") (pin "1") (pinfunction "1_1") (pintype "input"))
      (node (ref "U7") (pin "4") (pinfunction "4_4") (pintype "unspecified"))
    )
    (net (code "8") (name "HR_SU_SIGNAL_A") (class "Default")
      (node (ref "R12") (pin "2") (pinfunction "2_2") (pintype "input"))
      (node (ref "R13") (pin "1") (pinfunction "1_1") (pintype "input"))
      (node (ref "U1") (pin "23") (pinfunction "PA0-WKUP(PA0)_23") (pintype "bidirectional"))
    )
    (net (code "9") (name "HR_SU_SIGNAL_B") (class "Default")
      (node (ref "R15") (pin "2") (pinfunction "2_2") (pintype "input"))
      (node (ref "R16") (pin "1") (pinfunction "1_1") (pintype "input"))
      (node (ref "U1") (pin "24") (pinfunction "PA1_24") (pintype "bidirectional"))
    )
    (net (code "10") (name "HR_SU_SIGNAL_C") (class "Default")
      (node (ref "R18") (pin "2") (pinfunction "2_2") (pintype "input"))
      (node (ref "R19") (pin "1") (pinfunction "1_1") (pintype "input"))
      (node (ref "U1") (pin "25") (pinfunction "PA2_25") (pintype "bidirectional"))
    )
    (net (code "11") (name "NRST") (class "Default")
      (node (ref "C5") (pin "2") (pinfunction "2_2") (pintype "input"))
      (node (ref "SW1") (pin "2") (pinfunction "2_2") (pintype "unspecified"))
      (node (ref "U1") (pin "14") (pinfunction "NRST_14") (pintype "bidirectional"))
    )
    (net (code "12") (name "Net-(LED1-C)") (class "Default")
      (node (ref "LED1") (pin "1") (pinfunction "C_1") (pintype "input"))
      (node (ref "R21") (pin "2") (pinfunction "2_2") (pintype "input"))
    )
    (net (code "13") (name "Net-(R4-Pad2)") (class "Default")
      (node (ref "R4") (pin "2") (pinfunction "2_2") (pintype "input"))
      (node (ref "U3") (pin "2") (pinfunction "-IN_2") (pintype "unspecified"))
    )
    (net (code "14") (name "Net-(R10-Pad2)") (class "Default")
      (node (ref "R10") (pin "2") (pinfunction "2_2") (pintype "input"))
      (node (ref "R11") (pin "1") (pinfunction "1_1") (pintype "input"))
    )
    (net (code "15") (name "Net-(R13-Pad2)") (class "Default")
      (node (ref "R13") (pin "2") (pinfunction "2_2") (pintype "input"))
      (node (ref "R14") (pin "1") (pinfunction "1_1") (pintype "input"))
    )
    (net (code "16") (name "Net-(R16-Pad2)") (class "Default")
      (node (ref "R16") (pin "2") (pinfunction "2_2") (pintype "input"))
      (node (ref "R17") (pin "1") (pinfunction "1_1") (pintype "input"))
    )
    (net (code "17") (name "Net-(R19-Pad2)") (class "Default")
      (node (ref "R19") (pin "2") (pinfunction "2_2") (pintype "input"))
      (node (ref "R20") (pin "1") (pinfunction "1_1") (pintype "input"))
    )
    (net (code "18") (name "Net-(R36-Pad2)") (class "Default")
      (node (ref "R36") (pin "2") (pinfunction "2_2") (pintype "input"))
      (node (ref "R37") (pin "1") (pinfunction "1_1") (pintype "input"))
    )
    (net (code "19") (name "Net-(R40-Pad2)") (class "Default")
      (node (ref "R40") (pin "2") (pinfunction "2_2") (pintype "input"))
      (node (ref "R41") (pin "1") (pinfunction "1_1") (pintype "input"))
    )
    (net (code "20") (name "Net-(R43-Pad2)") (class "Default")
      (node (ref "R43") (pin "2") (pinfunction "2_2") (pintype "input"))
      (node (ref "R44") (pin "1") (pinfunction "1_1") (pintype "input"))
    )
    (net (code "21") (name "Net-(R46-Pad2)") (class "Default")
      (node (ref "R46") (pin "2") (pinfunction "2_2") (pintype "input"))
      (node (ref "R47") (pin "1") (pinfunction "1_1") (pintype "input"))
    )
    (net (code "22") (name "Net-(R49-Pad2)") (class "Default")
      (node (ref "R49") (pin "2") (pinfunction "2_2") (pintype "input"))
      (node (ref "R50") (pin "1") (pinfunction "1_1") (pintype "input"))
    )
    (net (code "23") (name "Net-(U1B-VBAT)") (class "Default")
      (node (ref "C4") (pin "1") (pinfunction "1_1") (pintype "input"))
      (node (ref "U1") (pin "6") (pinfunction "VBAT_6") (pintype "unspecified"))
    )
    (net (code "24") (name "Net-(U6-FB)") (class "Default")
      (node (ref "R22") (pin "2") (pinfunction "2_2") (pintype "input"))
      (node (ref "R23") (pin "1") (pinfunction "1_1") (pintype "input"))
      (node (ref "U6") (pin "5") (pinfunction "FB_5") (pintype "unspecified"))
    )
    (net (code "25") (name "Net-(U6-OUTP)") (class "Default")
      (node (ref "L1") (pin "2") (pinfunction "2_2") (pintype "unspecified"))
      (node (ref "U6") (pin "7") (pinfunction "OUTP_7") (pintype "unspecified"))
      (node (ref "U6") (pin "8") (pinfunction "SW_8") (pintype "unspecified"))
    )
    (net (code "26") (name "OSC_IN") (class "Default")
      (node (ref "C12") (pin "2") (pinfunction "2_2") (pintype "input"))
      (node (ref "U1") (pin "12") (pinfunction "PH0-OSC_IN(PH0)_12") (pintype "bidirectional"))
      (node (ref "X1") (pin "3") (pinfunction "OSC2_3") (pintype "unspecified"))
    )
    (net (code "27") (name "OSC_OUT") (class "Default")
      (node (ref "C13") (pin "2") (pinfunction "2_2") (pintype "input"))
      (node (ref "U1") (pin "13") (pinfunction "PH1-OSC_OUT(PH1)_13") (pintype "bidirectional"))
      (node (ref "X1") (pin "1") (pinfunction "OSC1_1") (pintype "unspecified"))
    )
    (net (code "28") (name "SENSOR1") (class "Default")
      (node (ref "R39") (pin "2") (pinfunction "2_2") (pintype "input"))
      (node (ref "R40") (pin "1") (pinfunction "1_1") (pintype "input"))
      (node (ref "U1") (pin "55") (pinfunction "PD8_55") (pintype "bidirectional"))
    )
    (net (code "29") (name "SENSOR1_SW") (class "Default")
      (node (ref "Q4") (pin "1") (pinfunction "G_1") (pintype "unspecified"))
      (node (ref "R52") (pin "2") (pinfunction "2_2") (pintype "input"))
      (node (ref "U1") (pin "51") (pinfunction "PB12_51") (pintype "bidirectional"))
    )
    (net (code "30") (name "SENSOR2") (class "Default")
      (node (ref "R42") (pin "2") (pinfunction "2_2") (pintype "input"))
      (node (ref "R43") (pin "1") (pinfunction "1_1") (pintype "input"))
      (node (ref "U1") (pin "56") (pinfunction "PD9_56") (pintype "bidirectional"))
    )
    (net (code "31") (name "SENSOR2_SW") (class "Default")
      (node (ref "Q5") (pin "1") (pinfunction "G_1") (pintype "unspecified"))
      (node (ref "R54") (pin "2") (pinfunction "2_2") (pintype "input"))
      (node (ref "U1") (pin "52") (pinfunction "PB13_52") (pintype "bidirectional"))
    )
    (net (code "32") (name "SENSOR3") (class "Default")
      (node (ref "R45") (pin "2") (pinfunction "2_2") (pintype "input"))
      (node (ref "R46") (pin "1") (pinfunction "1_1") (pintype "input"))
      (node (ref "U1") (pin "57") (pinfunction "PD10_57") (pintype "bidirectional"))
    )
    (net (code "33") (name "SENSOR3_SW") (class "Default")
      (node (ref "Q6") (pin "1") (pinfunction "G_1") (pintype "unspecified"))
      (node (ref "R56") (pin "2") (pinfunction "2_2") (pintype "input"))
      (node (ref "U1") (pin "53") (pinfunction "PB14_53") (pintype "bidirectional"))
    )
    (net (code "34") (name "SENSOR4") (class "Default")
      (node (ref "R48") (pin "2") (pinfunction "2_2") (pintype "input"))
      (node (ref "R49") (pin "1") (pinfunction "1_1") (pintype "input"))
      (node (ref "U1") (pin "85") (pinfunction "PD4_85") (pintype "bidirectional"))
    )
    (net (code "35") (name "SENSOR4_SW") (class "Default")
      (node (ref "Q7") (pin "1") (pinfunction "G_1") (pintype "unspecified"))
      (node (ref "R58") (pin "2") (pinfunction "2_2") (pintype "input"))
      (node (ref "U1") (pin "86") (pinfunction "PD5_86") (pintype "bidirectional"))
    )
    (net (code "36") (name "SENSOR_MOTOR1") (class "Default")
      (node (ref "CN10") (pin "2") (pinfunction "2_2") (pintype "unspecified"))
      (node (ref "Q4") (pin "3") (pinfunction "D_3") (pintype "unspecified"))
      (node (ref "R39") (pin "1") (pinfunction "1_1") (pintype "input"))
      (node (ref "R51") (pin "1") (pinfunction "1_1") (pintype "input"))
    )
    (net (code "37") (name "SENSOR_MOTOR2") (class "Default")
      (node (ref "CN12") (pin "2") (pinfunction "2_2") (pintype "unspecified"))
      (node (ref "Q5") (pin "3") (pinfunction "D_3") (pintype "unspecified"))
      (node (ref "R42") (pin "1") (pinfunction "1_1") (pintype "input"))
      (node (ref "R53") (pin "1") (pinfunction "1_1") (pintype "input"))
    )
    (net (code "38") (name "SENSOR_MOTOR3") (class "Default")
      (node (ref "CN11") (pin "2") (pinfunction "2_2") (pintype "unspecified"))
      (node (ref "Q6") (pin "3") (pinfunction "D_3") (pintype "unspecified"))
      (node (ref "R45") (pin "1") (pinfunction "1_1") (pintype "input"))
      (node (ref "R55") (pin "1") (pinfunction "1_1") (pintype "input"))
    )
    (net (code "39") (name "SENSOR_MOTOR4") (class "Default")
      (node (ref "CN13") (pin "2") (pinfunction "2_2") (pintype "unspecified"))
      (node (ref "Q7") (pin "3") (pinfunction "D_3") (pintype "unspecified"))
      (node (ref "R48") (pin "1") (pinfunction "1_1") (pintype "input"))
      (node (ref "R57") (pin "1") (pinfunction "1_1") (pintype "input"))
    )
    (net (code "40") (name "SV") (class "Default")
      (node (ref "CN3") (pin "2") (pinfunction "2_2") (pintype "unspecified"))
      (node (ref "R3") (pin "2") (pinfunction "2_2") (pintype "input"))
      (node (ref "U3") (pin "1") (pinfunction "OUT_1") (pintype "unspecified"))
    )
    (net (code "41") (name "SV_DACOUT") (class "Default")
      (node (ref "U1") (pin "26") (pinfunction "PA3_26") (pintype "bidirectional"))
      (node (ref "U3") (pin "3") (pinfunction "+IN_3") (pintype "unspecified"))
    )
    (net (code "42") (name "SWCLK") (class "Default")
      (node (ref "H1") (pin "4") (pinfunction "4_4") (pintype "unspecified"))
      (node (ref "U1") (pin "76") (pinfunction "PA14(JTCK-SWCLK)_76") (pintype "bidirectional"))
    )
    (net (code "43") (name "SWDIO") (class "Default")
      (node (ref "H1") (pin "3") (pinfunction "3_3") (pintype "unspecified"))
      (node (ref "U1") (pin "72") (pinfunction "PA13(JTMS-SWDIO)_72") (pintype "bidirectional"))
    )
    (net (code "44") (name "USART_RX") (class "Default")
      (node (ref "CN9") (pin "3") (pinfunction "3_3") (pintype "unspecified"))
      (node (ref "U1") (pin "69") (pinfunction "PA10_69") (pintype "bidirectional"))
    )
    (net (code "45") (name "USART_TX") (class "Default")
      (node (ref "CN9") (pin "2") (pinfunction "2_2") (pintype "unspecified"))
      (node (ref "U1") (pin "68") (pinfunction "PA9_68") (pintype "bidirectional"))
    )
    (net (code "46") (name "VCC_3.3V") (class "Default")
      (node (ref "C10") (pin "2") (pinfunction "2_2") (pintype "input"))
      (node (ref "C11") (pin "2") (pinfunction "2_2") (pintype "input"))
      (node (ref "C3") (pin "1") (pinfunction "1_1") (pintype "input"))
      (node (ref "C6") (pin "1") (pinfunction "1_1") (pintype "input"))
      (node (ref "C7") (pin "2") (pinfunction "2_2") (pintype "input"))
      (node (ref "C8") (pin "2") (pinfunction "2_2") (pintype "input"))
      (node (ref "C9") (pin "2") (pinfunction "2_2") (pintype "input"))
      (node (ref "H1") (pin "1") (pinfunction "1_1") (pintype "unspecified"))
      (node (ref "LED1") (pin "2") (pinfunction "A_2") (pintype "input"))
      (node (ref "U1") (pin "100") (pinfunction "VDD_100") (pintype "unspecified"))
      (node (ref "U1") (pin "11") (pinfunction "VDD_11") (pintype "unspecified"))
      (node (ref "U1") (pin "19") (pinfunction "VDD_19") (pintype "unspecified"))
      (node (ref "U1") (pin "21") (pinfunction "VREF+_21") (pintype "unspecified"))
      (node (ref "U1") (pin "22") (pinfunction "VDDA_22") (pintype "unspecified"))
      (node (ref "U1") (pin "28") (pinfunction "VDD_28") (pintype "unspecified"))
      (node (ref "U1") (pin "50") (pinfunction "VDD_50") (pintype "unspecified"))
      (node (ref "U1") (pin "75") (pinfunction "VDD_75") (pintype "unspecified"))
      (node (ref "U2") (pin "2") (pinfunction "VOUT_2") (pintype "unspecified"))
      (node (ref "U2") (pin "4") (pinfunction "VOUT_4") (pintype "unspecified"))
    )
    (net (code "47") (name "VCC_21V") (class "Default")
      (node (ref "C16") (pin "2") (pinfunction "2_2") (pintype "input"))
      (node (ref "CN10") (pin "1") (pinfunction "1_1") (pintype "unspecified"))
      (node (ref "CN11") (pin "1") (pinfunction "1_1") (pintype "unspecified"))
      (node (ref "CN12") (pin "1") (pinfunction "1_1") (pintype "unspecified"))
      (node (ref "CN13") (pin "1") (pinfunction "1_1") (pintype "unspecified"))
      (node (ref "R23") (pin "2") (pinfunction "2_2") (pintype "input"))
      (node (ref "R51") (pin "2") (pinfunction "2_2") (pintype "input"))
      (node (ref "R53") (pin "2") (pinfunction "2_2") (pintype "input"))
      (node (ref "R55") (pin "2") (pinfunction "2_2") (pintype "input"))
      (node (ref "R57") (pin "2") (pinfunction "2_2") (pintype "input"))
      (node (ref "U6") (pin "3") (pinfunction "OUTN_3") (pintype "unspecified"))
    )
    (net (code "48") (name "X0") (class "Default")
      (node (ref "CN5") (pin "1") (pinfunction "1_1") (pintype "unspecified"))
      (node (ref "Q2") (pin "3") (pinfunction "D_3") (pintype "unspecified"))
      (node (ref "R29") (pin "1") (pinfunction "1_1") (pintype "input"))
    )
    (net (code "49") (name "X0_START_STOP") (class "Default")
      (node (ref "Q2") (pin "1") (pinfunction "G_1") (pintype "unspecified"))
      (node (ref "R30") (pin "2") (pinfunction "2_2") (pintype "input"))
      (node (ref "U1") (pin "83") (pinfunction "PD2_83") (pintype "bidirectional"))
    )
    (net (code "50") (name "X1") (class "Default")
      (node (ref "CN4") (pin "1") (pinfunction "1_1") (pintype "unspecified"))
      (node (ref "Q1") (pin "3") (pinfunction "D_3") (pintype "unspecified"))
      (node (ref "R26") (pin "1") (pinfunction "1_1") (pintype "input"))
    )
    (net (code "51") (name "X1_MOT_DIR") (class "Default")
      (node (ref "Q1") (pin "1") (pinfunction "G_1") (pintype "unspecified"))
      (node (ref "R27") (pin "2") (pinfunction "2_2") (pintype "input"))
      (node (ref "U1") (pin "82") (pinfunction "PD1_82") (pintype "bidirectional"))
    )
    (net (code "52") (name "X2") (class "Default")
      (node (ref "CN2") (pin "2") (pinfunction "2_2") (pintype "unspecified"))
      (node (ref "Q3") (pin "3") (pinfunction "D_3") (pintype "unspecified"))
      (node (ref "R32") (pin "1") (pinfunction "1_1") (pintype "input"))
      (node (ref "R9") (pin "1") (pinfunction "1_1") (pintype "input"))
    )
    (net (code "53") (name "X2_SIGNAL_INPUT") (class "Default")
      (node (ref "R10") (pin "1") (pinfunction "1_1") (pintype "input"))
      (node (ref "R9") (pin "2") (pinfunction "2_2") (pintype "input"))
    )
    (net (code "54") (name "X2_SIGNAL_TO_MOTOR") (class "Default")
      (node (ref "Q3") (pin "1") (pinfunction "G_1") (pintype "unspecified"))
      (node (ref "R33") (pin "2") (pinfunction "2_2") (pintype "input"))
      (node (ref "U1") (pin "81") (pinfunction "PD0_81") (pintype "bidirectional"))
    )
    (net (code "55") (name "Y0") (class "Default")
      (node (ref "CN6") (pin "1") (pinfunction "1_1") (pintype "unspecified"))
      (node (ref "R35") (pin "1") (pinfunction "1_1") (pintype "input"))
      (node (ref "R38") (pin "1") (pinfunction "1_1") (pintype "input"))
    )
    (net (code "56") (name "Y0_ALARM") (class "Default")
      (node (ref "R35") (pin "2") (pinfunction "2_2") (pintype "input"))
      (node (ref "R36") (pin "1") (pinfunction "1_1") (pintype "input"))
      (node (ref "U1") (pin "84") (pinfunction "PD3_84") (pintype "bidirectional"))
    )
    (net (code "57") (name "unconnected-(CN1-Pad2)") (class "Default")
      (node (ref "CN1") (pin "2") (pinfunction "2_2") (pintype "unspecified+no_connect"))
    )
    (net (code "58") (name "unconnected-(CN1-Pad3)") (class "Default")
      (node (ref "CN1") (pin "3") (pinfunction "3_3") (pintype "unspecified+no_connect"))
    )
    (net (code "59") (name "unconnected-(U1A-PA4-Pad29)") (class "Default")
      (node (ref "U1") (pin "29") (pinfunction "PA4_29") (pintype "bidirectional+no_connect"))
    )
    (net (code "60") (name "unconnected-(U1A-PA5-Pad30)") (class "Default")
      (node (ref "U1") (pin "30") (pinfunction "PA5_30") (pintype "bidirectional+no_connect"))
    )
    (net (code "61") (name "unconnected-(U1A-PA6-Pad31)") (class "Default")
      (node (ref "U1") (pin "31") (pinfunction "PA6_31") (pintype "bidirectional+no_connect"))
    )
    (net (code "62") (name "unconnected-(U1A-PA7-Pad32)") (class "Default")
      (node (ref "U1") (pin "32") (pinfunction "PA7_32") (pintype "bidirectional+no_connect"))
    )
    (net (code "63") (name "unconnected-(U1A-PA8-Pad67)") (class "Default")
      (node (ref "U1") (pin "67") (pinfunction "PA8_67") (pintype "bidirectional+no_connect"))
    )
    (net (code "64") (name "unconnected-(U1A-PA11-Pad70)") (class "Default")
      (node (ref "U1") (pin "70") (pinfunction "PA11_70") (pintype "bidirectional+no_connect"))
    )
    (net (code "65") (name "unconnected-(U1A-PA12-Pad71)") (class "Default")
      (node (ref "U1") (pin "71") (pinfunction "PA12_71") (pintype "bidirectional+no_connect"))
    )
    (net (code "66") (name "unconnected-(U1A-PA15(JTDI)-Pad77)") (class "Default")
      (node (ref "U1") (pin "77") (pinfunction "PA15(JTDI)_77") (pintype "bidirectional+no_connect"))
    )
    (net (code "67") (name "unconnected-(U1A-PB0-Pad35)") (class "Default")
      (node (ref "U1") (pin "35") (pinfunction "PB0_35") (pintype "bidirectional+no_connect"))
    )
    (net (code "68") (name "unconnected-(U1A-PB1-Pad36)") (class "Default")
      (node (ref "U1") (pin "36") (pinfunction "PB1_36") (pintype "bidirectional+no_connect"))
    )
    (net (code "69") (name "unconnected-(U1A-PB3(JTDOTRACESWO)-Pad89)") (class "Default")
      (node (ref "U1") (pin "89") (pinfunction "PB3(JTDOTRACESWO)_89") (pintype "bidirectional+no_connect"))
    )
    (net (code "70") (name "unconnected-(U1A-PB4(NJTRST)-Pad90)") (class "Default")
      (node (ref "U1") (pin "90") (pinfunction "PB4(NJTRST)_90") (pintype "bidirectional+no_connect"))
    )
    (net (code "71") (name "unconnected-(U1A-PB5-Pad91)") (class "Default")
      (node (ref "U1") (pin "91") (pinfunction "PB5_91") (pintype "bidirectional+no_connect"))
    )
    (net (code "72") (name "unconnected-(U1A-PB6-Pad92)") (class "Default")
      (node (ref "U1") (pin "92") (pinfunction "PB6_92") (pintype "bidirectional+no_connect"))
    )
    (net (code "73") (name "unconnected-(U1A-PB7-Pad93)") (class "Default")
      (node (ref "U1") (pin "93") (pinfunction "PB7_93") (pintype "bidirectional+no_connect"))
    )
    (net (code "74") (name "unconnected-(U1A-PB8-Pad95)") (class "Default")
      (node (ref "U1") (pin "95") (pinfunction "PB8_95") (pintype "bidirectional+no_connect"))
    )
    (net (code "75") (name "unconnected-(U1A-PB9-Pad96)") (class "Default")
      (node (ref "U1") (pin "96") (pinfunction "PB9_96") (pintype "bidirectional+no_connect"))
    )
    (net (code "76") (name "unconnected-(U1A-PB10-Pad47)") (class "Default")
      (node (ref "U1") (pin "47") (pinfunction "PB10_47") (pintype "bidirectional+no_connect"))
    )
    (net (code "77") (name "unconnected-(U1A-PB11-Pad48)") (class "Default")
      (node (ref "U1") (pin "48") (pinfunction "PB11_48") (pintype "bidirectional+no_connect"))
    )
    (net (code "78") (name "unconnected-(U1A-PB15-Pad54)") (class "Default")
      (node (ref "U1") (pin "54") (pinfunction "PB15_54") (pintype "bidirectional+no_connect"))
    )
    (net (code "79") (name "unconnected-(U1A-PC0-Pad15)") (class "Default")
      (node (ref "U1") (pin "15") (pinfunction "PC0_15") (pintype "bidirectional+no_connect"))
    )
    (net (code "80") (name "unconnected-(U1A-PC1-Pad16)") (class "Default")
      (node (ref "U1") (pin "16") (pinfunction "PC1_16") (pintype "bidirectional+no_connect"))
    )
    (net (code "81") (name "unconnected-(U1A-PC2-Pad17)") (class "Default")
      (node (ref "U1") (pin "17") (pinfunction "PC2_17") (pintype "bidirectional+no_connect"))
    )
    (net (code "82") (name "unconnected-(U1A-PC3-Pad18)") (class "Default")
      (node (ref "U1") (pin "18") (pinfunction "PC3_18") (pintype "bidirectional+no_connect"))
    )
    (net (code "83") (name "unconnected-(U1A-PC4-Pad33)") (class "Default")
      (node (ref "U1") (pin "33") (pinfunction "PC4_33") (pintype "bidirectional+no_connect"))
    )
    (net (code "84") (name "unconnected-(U1A-PC5-Pad34)") (class "Default")
      (node (ref "U1") (pin "34") (pinfunction "PC5_34") (pintype "bidirectional+no_connect"))
    )
    (net (code "85") (name "unconnected-(U1A-PC6-Pad63)") (class "Default")
      (node (ref "U1") (pin "63") (pinfunction "PC6_63") (pintype "bidirectional+no_connect"))
    )
    (net (code "86") (name "unconnected-(U1A-PC7-Pad64)") (class "Default")
      (node (ref "U1") (pin "64") (pinfunction "PC7_64") (pintype "bidirectional+no_connect"))
    )
    (net (code "87") (name "unconnected-(U1A-PC8-Pad65)") (class "Default")
      (node (ref "U1") (pin "65") (pinfunction "PC8_65") (pintype "bidirectional+no_connect"))
    )
    (net (code "88") (name "unconnected-(U1A-PC9-Pad66)") (class "Default")
      (node (ref "U1") (pin "66") (pinfunction "PC9_66") (pintype "bidirectional+no_connect"))
    )
    (net (code "89") (name "unconnected-(U1A-PC10-Pad78)") (class "Default")
      (node (ref "U1") (pin "78") (pinfunction "PC10_78") (pintype "bidirectional+no_connect"))
    )
    (net (code "90") (name "unconnected-(U1A-PC11-Pad79)") (class "Default")
      (node (ref "U1") (pin "79") (pinfunction "PC11_79") (pintype "bidirectional+no_connect"))
    )
    (net (code "91") (name "unconnected-(U1A-PC12-Pad80)") (class "Default")
      (node (ref "U1") (pin "80") (pinfunction "PC12_80") (pintype "bidirectional+no_connect"))
    )
    (net (code "92") (name "unconnected-(U1A-PC13-Pad7)") (class "Default")
      (node (ref "U1") (pin "7") (pinfunction "PC13_7") (pintype "bidirectional+no_connect"))
    )
    (net (code "93") (name "unconnected-(U1A-PC14-OSC32_IN(PC14)-Pad8)") (class "Default")
      (node (ref "U1") (pin "8") (pinfunction "PC14-OSC32_IN(PC14)_8") (pintype "bidirectional+no_connect"))
    )
    (net (code "94") (name "unconnected-(U1A-PC15-OSC32_OUT(PC15)-Pad9)") (class "Default")
      (node (ref "U1") (pin "9") (pinfunction "PC15-OSC32_OUT(PC15)_9") (pintype "bidirectional+no_connect"))
    )
    (net (code "95") (name "unconnected-(U1A-PD6-Pad87)") (class "Default")
      (node (ref "U1") (pin "87") (pinfunction "PD6_87") (pintype "bidirectional+no_connect"))
    )
    (net (code "96") (name "unconnected-(U1A-PD7-Pad88)") (class "Default")
      (node (ref "U1") (pin "88") (pinfunction "PD7_88") (pintype "bidirectional+no_connect"))
    )
    (net (code "97") (name "unconnected-(U1A-PD11-Pad58)") (class "Default")
      (node (ref "U1") (pin "58") (pinfunction "PD11_58") (pintype "bidirectional+no_connect"))
    )
    (net (code "98") (name "unconnected-(U1A-PD12-Pad59)") (class "Default")
      (node (ref "U1") (pin "59") (pinfunction "PD12_59") (pintype "bidirectional+no_connect"))
    )
    (net (code "99") (name "unconnected-(U1A-PD13-Pad60)") (class "Default")
      (node (ref "U1") (pin "60") (pinfunction "PD13_60") (pintype "bidirectional+no_connect"))
    )
    (net (code "100") (name "unconnected-(U1A-PD14-Pad61)") (class "Default")
      (node (ref "U1") (pin "61") (pinfunction "PD14_61") (pintype "bidirectional+no_connect"))
    )
    (net (code "101") (name "unconnected-(U1A-PD15-Pad62)") (class "Default")
      (node (ref "U1") (pin "62") (pinfunction "PD15_62") (pintype "bidirectional+no_connect"))
    )
    (net (code "102") (name "unconnected-(U1A-PE0-Pad97)") (class "Default")
      (node (ref "U1") (pin "97") (pinfunction "PE0_97") (pintype "bidirectional+no_connect"))
    )
    (net (code "103") (name "unconnected-(U1A-PE1-Pad98)") (class "Default")
      (node (ref "U1") (pin "98") (pinfunction "PE1_98") (pintype "bidirectional+no_connect"))
    )
    (net (code "104") (name "unconnected-(U1A-PE2-Pad1)") (class "Default")
      (node (ref "U1") (pin "1") (pinfunction "PE2_1") (pintype "bidirectional+no_connect"))
    )
    (net (code "105") (name "unconnected-(U1A-PE3-Pad2)") (class "Default")
      (node (ref "U1") (pin "2") (pinfunction "PE3_2") (pintype "bidirectional+no_connect"))
    )
    (net (code "106") (name "unconnected-(U1A-PE4-Pad3)") (class "Default")
      (node (ref "U1") (pin "3") (pinfunction "PE4_3") (pintype "bidirectional+no_connect"))
    )
    (net (code "107") (name "unconnected-(U1A-PE5-Pad4)") (class "Default")
      (node (ref "U1") (pin "4") (pinfunction "PE5_4") (pintype "bidirectional+no_connect"))
    )
    (net (code "108") (name "unconnected-(U1A-PE6-Pad5)") (class "Default")
      (node (ref "U1") (pin "5") (pinfunction "PE6_5") (pintype "bidirectional+no_connect"))
    )
    (net (code "109") (name "unconnected-(U1A-PE7-Pad38)") (class "Default")
      (node (ref "U1") (pin "38") (pinfunction "PE7_38") (pintype "bidirectional+no_connect"))
    )
    (net (code "110") (name "unconnected-(U1A-PE8-Pad39)") (class "Default")
      (node (ref "U1") (pin "39") (pinfunction "PE8_39") (pintype "bidirectional+no_connect"))
    )
    (net (code "111") (name "unconnected-(U1A-PE9-Pad40)") (class "Default")
      (node (ref "U1") (pin "40") (pinfunction "PE9_40") (pintype "bidirectional+no_connect"))
    )
    (net (code "112") (name "unconnected-(U1A-PE10-Pad41)") (class "Default")
      (node (ref "U1") (pin "41") (pinfunction "PE10_41") (pintype "bidirectional+no_connect"))
    )
    (net (code "113") (name "unconnected-(U1A-PE11-Pad42)") (class "Default")
      (node (ref "U1") (pin "42") (pinfunction "PE11_42") (pintype "bidirectional+no_connect"))
    )
    (net (code "114") (name "unconnected-(U1A-PE12-Pad43)") (class "Default")
      (node (ref "U1") (pin "43") (pinfunction "PE12_43") (pintype "bidirectional+no_connect"))
    )
    (net (code "115") (name "unconnected-(U1A-PE13-Pad44)") (class "Default")
      (node (ref "U1") (pin "44") (pinfunction "PE13_44") (pintype "bidirectional+no_connect"))
    )
    (net (code "116") (name "unconnected-(U1A-PE14-Pad45)") (class "Default")
      (node (ref "U1") (pin "45") (pinfunction "PE14_45") (pintype "bidirectional+no_connect"))
    )
    (net (code "117") (name "unconnected-(U1A-PE15-Pad46)") (class "Default")
      (node (ref "U1") (pin "46") (pinfunction "PE15_46") (pintype "bidirectional+no_connect"))
    )
    (net (code "118") (name "unconnected-(U1A-VCAP_1-Pad49)") (class "Default")
      (node (ref "U1") (pin "49") (pinfunction "VCAP_1_49") (pintype "unspecified+no_connect"))
    )
    (net (code "119") (name "unconnected-(U1A-VCAP_2-Pad73)") (class "Default")
      (node (ref "U1") (pin "73") (pinfunction "VCAP_2_73") (pintype "unspecified+no_connect"))
    )
    (net (code "120") (name "unconnected-(U3-+IN-Pad5)") (class "Default")
      (node (ref "U3") (pin "5") (pinfunction "+IN_5") (pintype "unspecified+no_connect"))
    )
    (net (code "121") (name "unconnected-(U3--IN-Pad6)") (class "Default")
      (node (ref "U3") (pin "6") (pinfunction "-IN_6") (pintype "unspecified+no_connect"))
    )
    (net (code "122") (name "unconnected-(U3-OUT-Pad7)") (class "Default")
      (node (ref "U3") (pin "7") (pinfunction "OUT_7") (pintype "unspecified+no_connect"))
    )
  )
)
